# MultiSpikeHoldSchem.net
KiCad netlist of a schematic drawn in Altium Designer
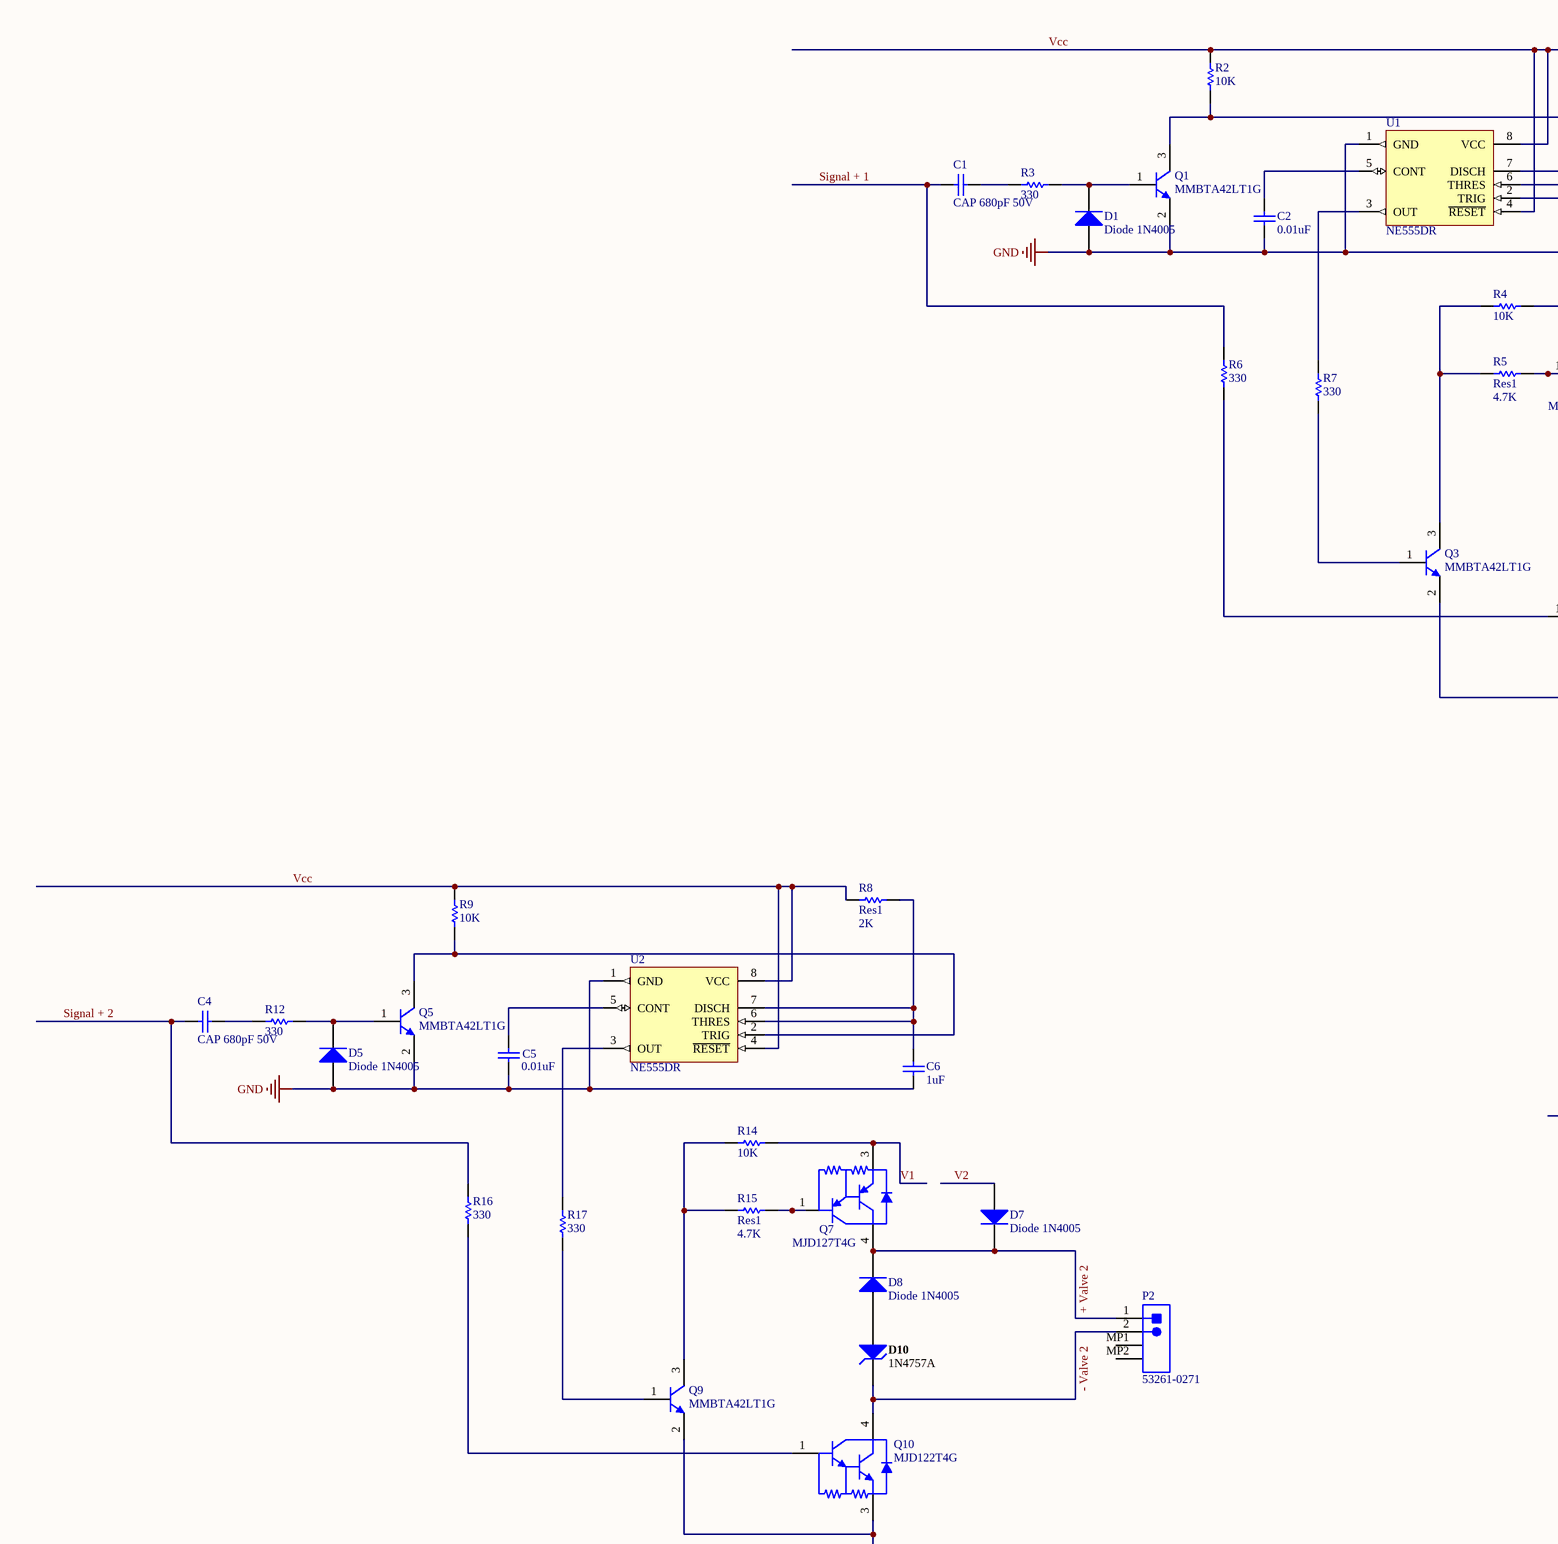
[diagram p0: MultiSpikeHoldSchem.SchDoc, top left]
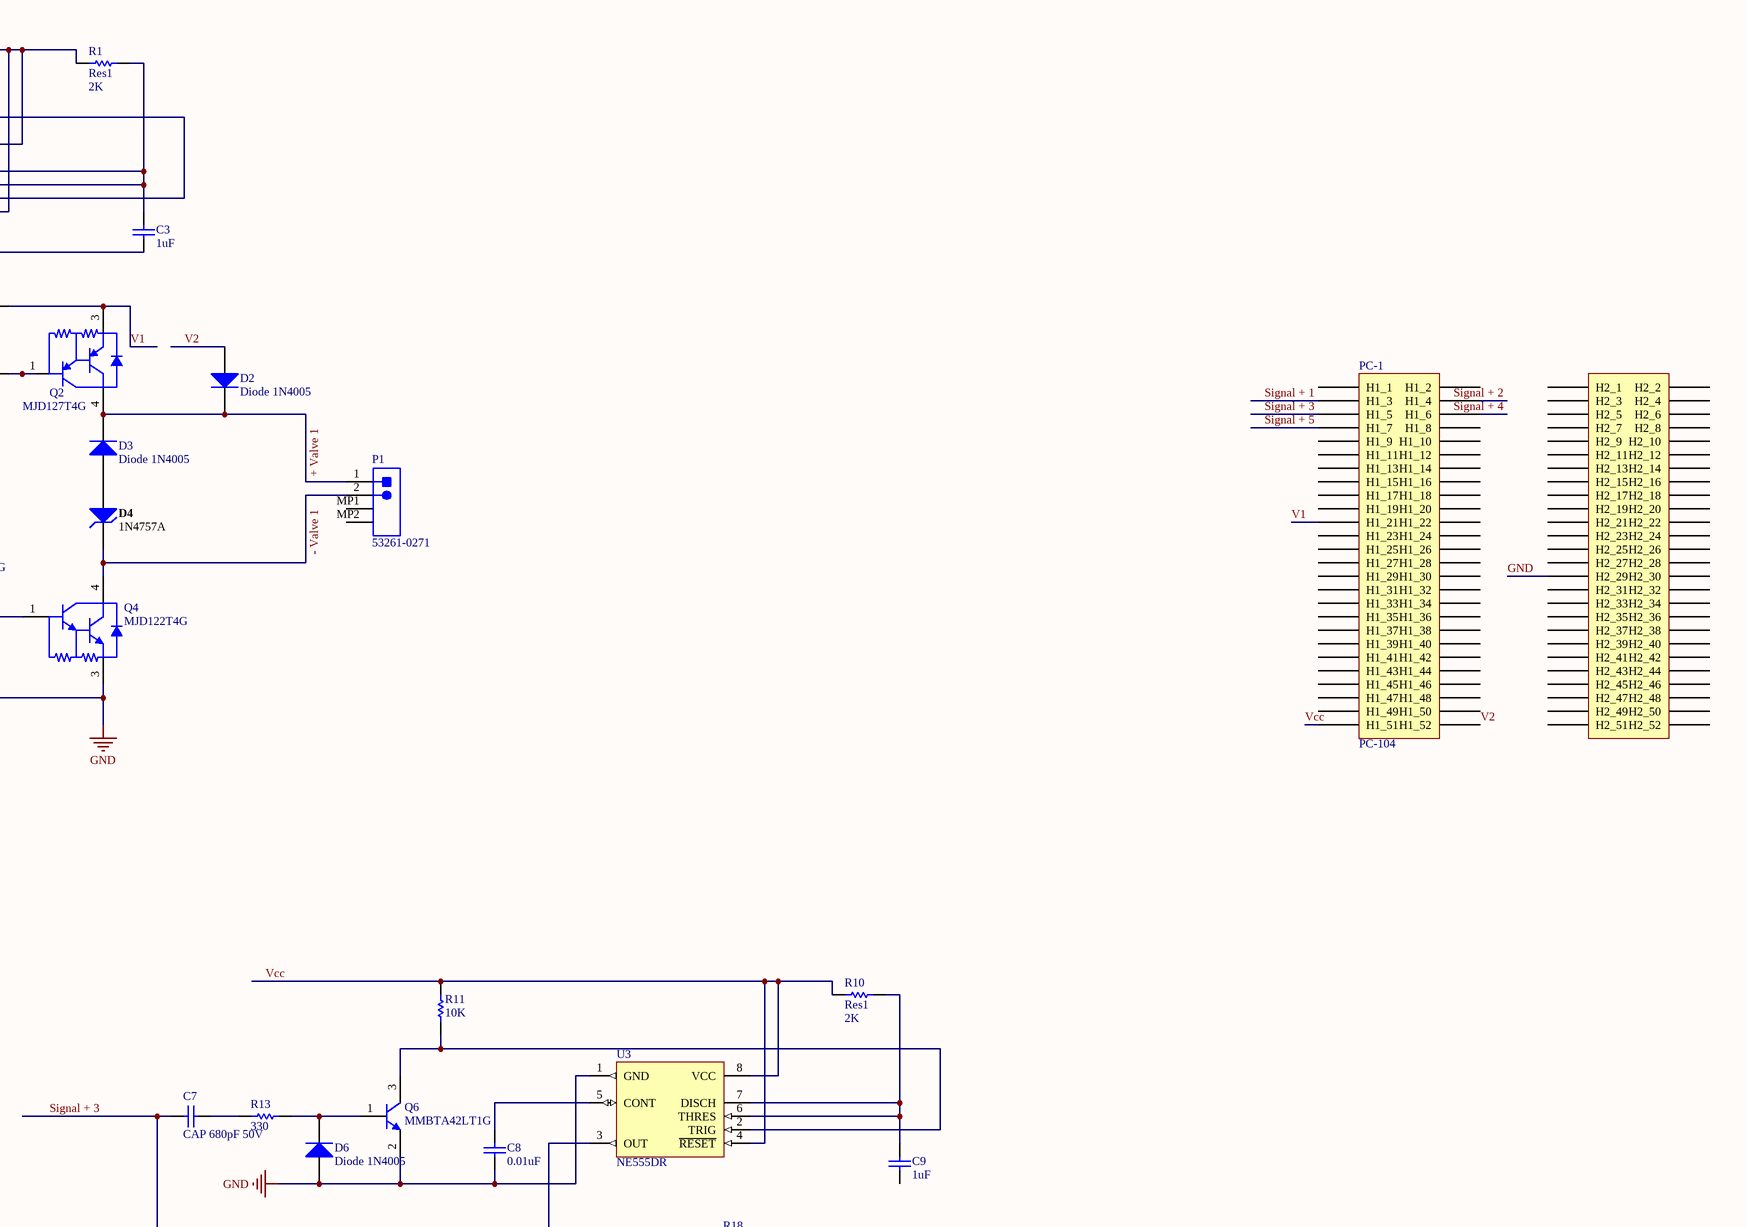
[diagram p1: MultiSpikeHoldSchem.SchDoc, top right]
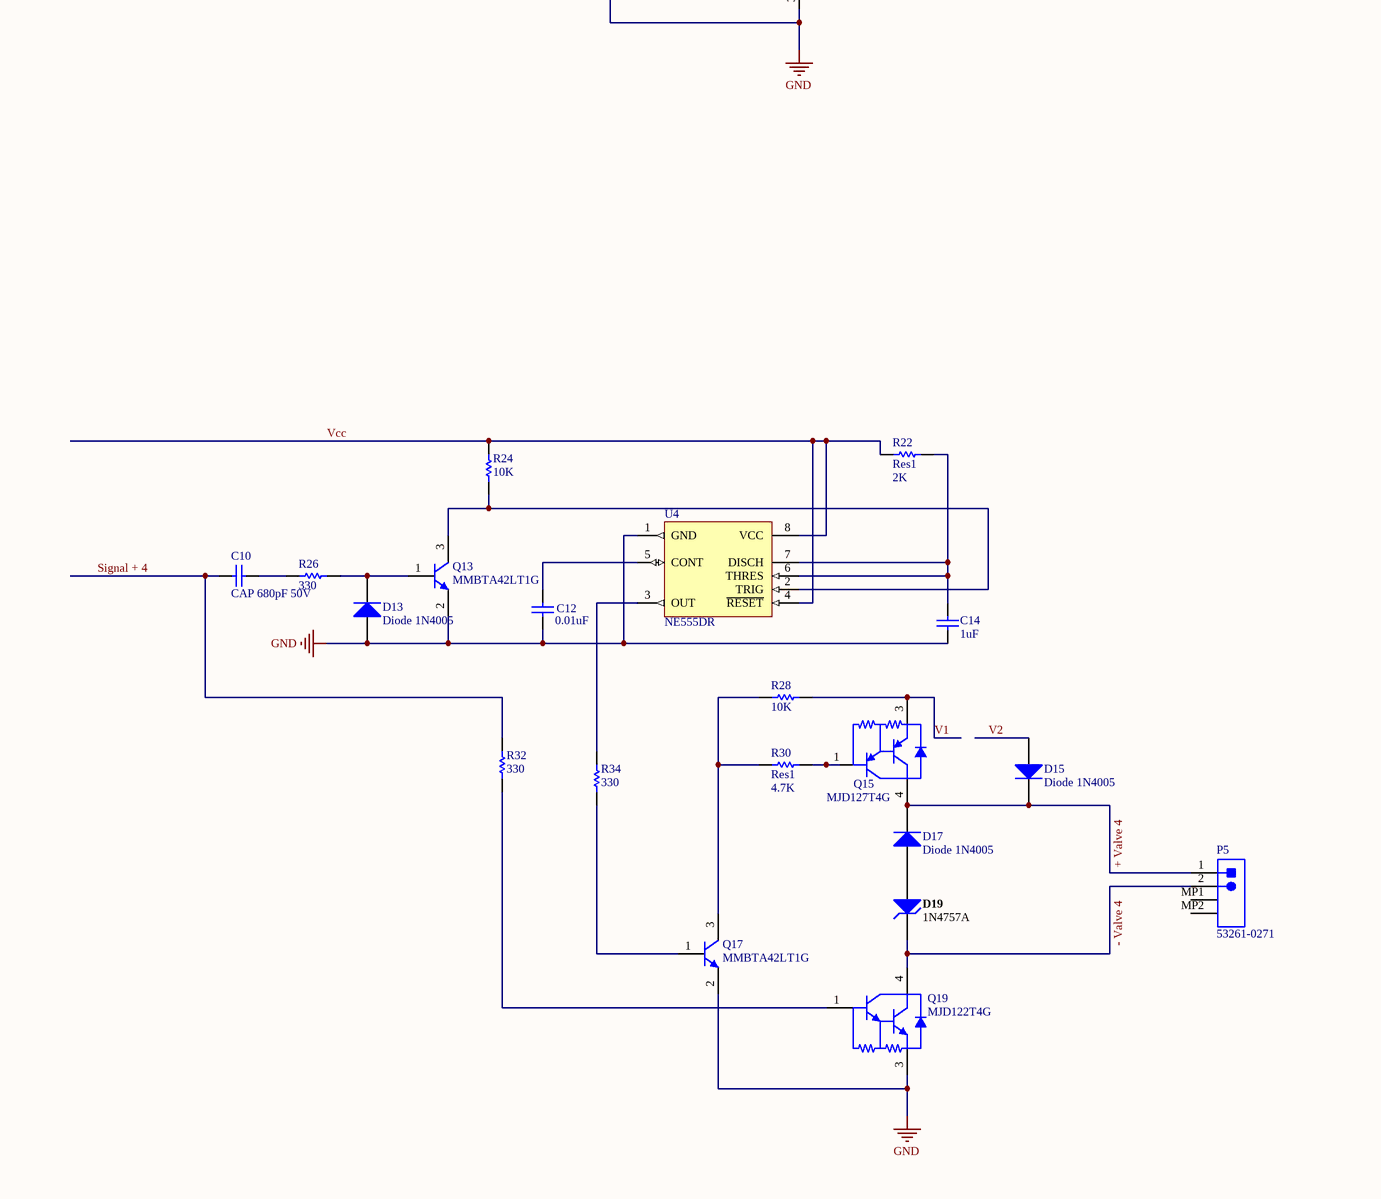
[diagram p2: MultiSpikeHoldSchem.SchDoc, bottom left]
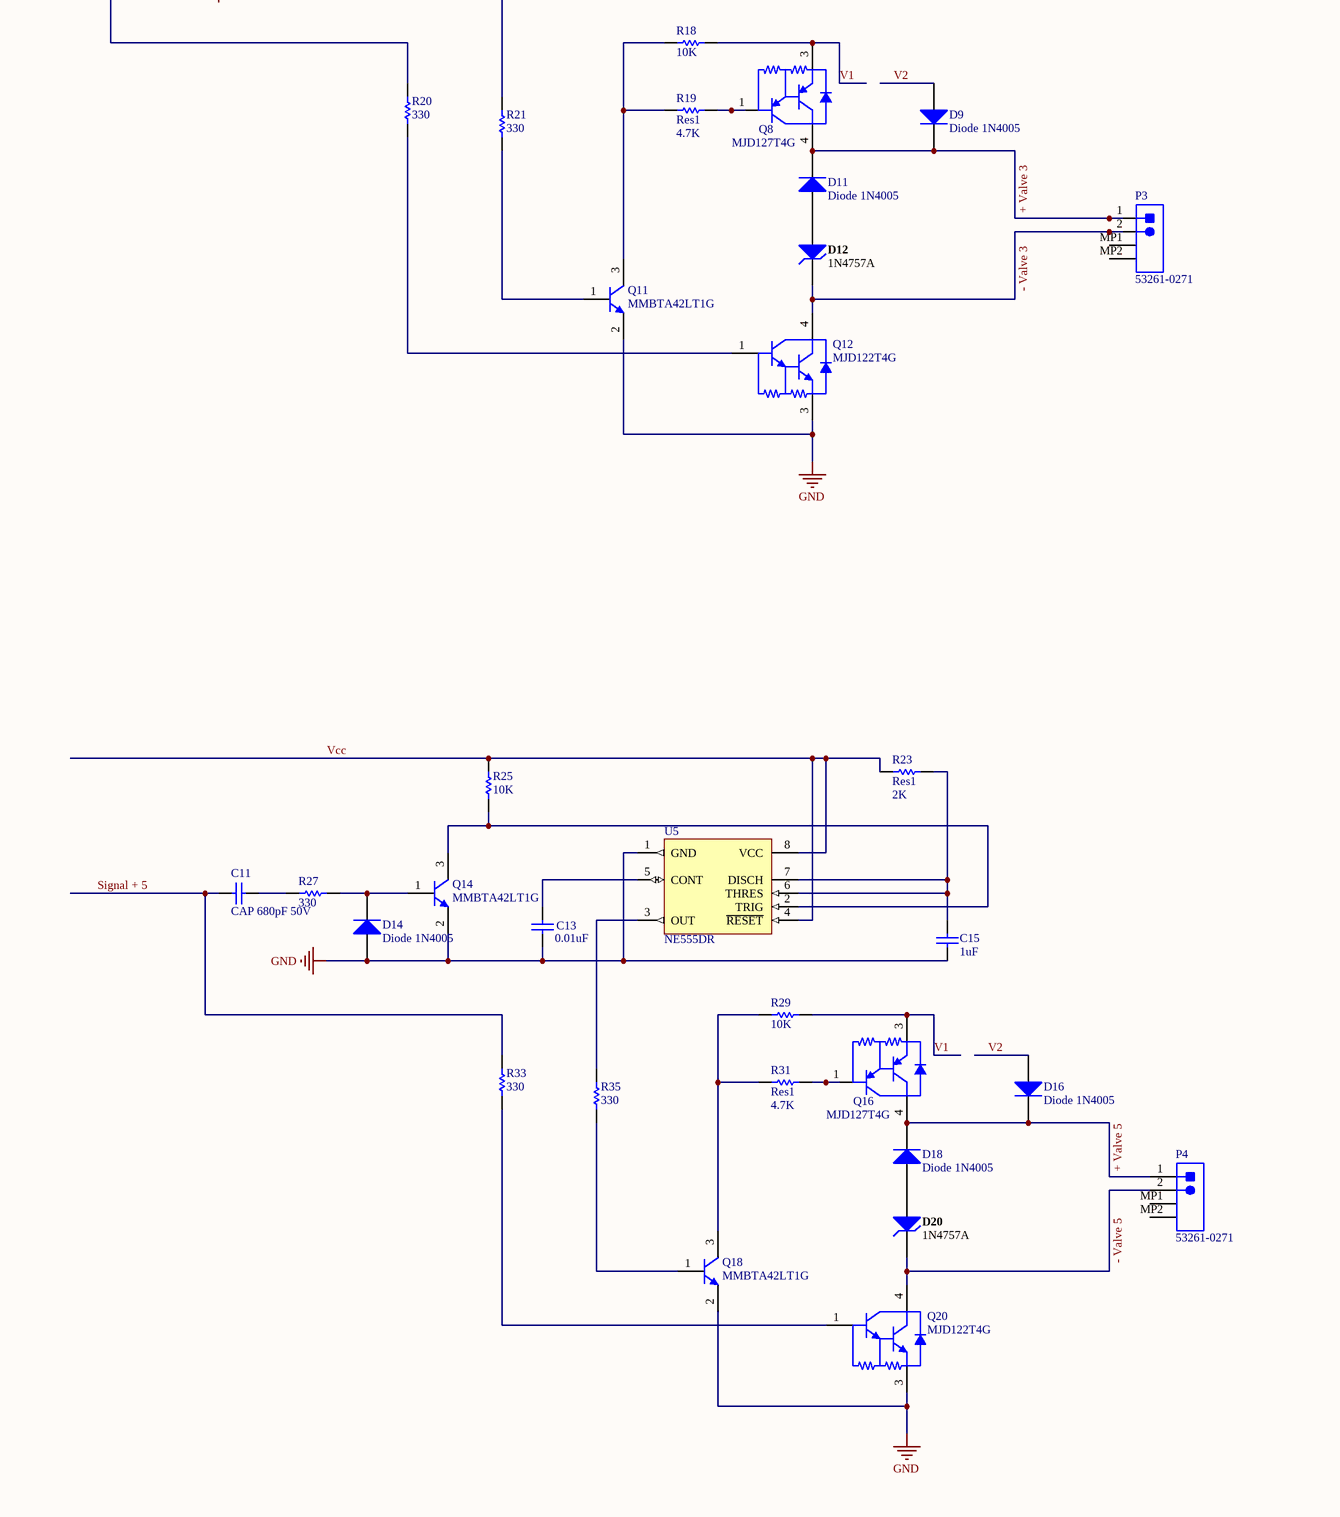
[diagram p3: MultiSpikeHoldSchem.SchDoc, bottom right]

(export (version "E")
  (design (tool "Eeschema 10.0.6"))
  (components
    (comp (ref "C1")
      (value "CAP 680pF 50V")
      (footprint "CAPC1812(4532)230_L")
      (description "CAP 680pF 50V ±5% 1812 (4532 Metric) Thickness 2.3mm SMD")
      (fields (field (name "TOLERANCE") "Â±5%"))
      (libsource (lib "Altium Content Vault") (part "CAP"))
    )
    (comp (ref "C2")
      (value "0.01uF")
      (footprint "CAPC2013X70X45ML10T25")
      (description "Chip Capacitor, 10 nF, +/- 10%, 50 V, -55 to 125 degC, 0805 (2012 Metric), RoHS, Tape and Reel")
      (fields (field (name "TOLERANCE") "10%") (field (name "MANUFACTURER") "Murata"))
      (libsource (lib "Altium Content Vault") (part "CAP-NP-2"))
    )
    (comp (ref "C3")
      (value "1uF")
      (footprint "CAPC1206(3216)110_L")
      (description "CAP 1uF 50V ±10% 1206 (3216 Metric) Thickness 1.1mm SMD")
      (fields (field (name "TOLERANCE") "Â±10%"))
      (libsource (lib "Altium Content Vault") (part "CAP"))
    )
    (comp (ref "C4")
      (value "CAP 680pF 50V")
      (footprint "CAPC1812(4532)230_L")
      (description "CAP 680pF 50V ±5% 1812 (4532 Metric) Thickness 2.3mm SMD")
      (fields (field (name "TOLERANCE") "Â±5%"))
      (libsource (lib "Altium Content Vault") (part "CAP"))
    )
    (comp (ref "C5")
      (value "0.01uF")
      (footprint "CAPC2013X70X45ML10T25")
      (description "Chip Capacitor, 10 nF, +/- 10%, 50 V, -55 to 125 degC, 0805 (2012 Metric), RoHS, Tape and Reel")
      (fields (field (name "TOLERANCE") "10%") (field (name "MANUFACTURER") "Murata"))
      (libsource (lib "Altium Content Vault") (part "CAP-NP-2"))
    )
    (comp (ref "C6")
      (value "1uF")
      (footprint "CAPC1206(3216)110_L")
      (description "CAP 1uF 50V ±10% 1206 (3216 Metric) Thickness 1.1mm SMD")
      (fields (field (name "TOLERANCE") "Â±10%"))
      (libsource (lib "Altium Content Vault") (part "CAP"))
    )
    (comp (ref "C7")
      (value "CAP 680pF 50V")
      (footprint "CAPC1812(4532)230_L")
      (description "CAP 680pF 50V ±5% 1812 (4532 Metric) Thickness 2.3mm SMD")
      (fields (field (name "TOLERANCE") "Â±5%"))
      (libsource (lib "Altium Content Vault") (part "CAP"))
    )
    (comp (ref "C8")
      (value "0.01uF")
      (footprint "CAPC2013X70X45ML10T25")
      (description "Chip Capacitor, 10 nF, +/- 10%, 50 V, -55 to 125 degC, 0805 (2012 Metric), RoHS, Tape and Reel")
      (fields (field (name "TOLERANCE") "10%") (field (name "MANUFACTURER") "Murata"))
      (libsource (lib "Altium Content Vault") (part "CAP-NP-2"))
    )
    (comp (ref "C9")
      (value "1uF")
      (footprint "CAPC1206(3216)110_L")
      (description "CAP 1uF 50V ±10% 1206 (3216 Metric) Thickness 1.1mm SMD")
      (fields (field (name "TOLERANCE") "Â±10%"))
      (libsource (lib "Altium Content Vault") (part "CAP"))
    )
    (comp (ref "C10")
      (value "CAP 680pF 50V")
      (footprint "CAPC1812(4532)230_L")
      (description "CAP 680pF 50V ±5% 1812 (4532 Metric) Thickness 2.3mm SMD")
      (fields (field (name "TOLERANCE") "Â±5%"))
      (libsource (lib "Altium Content Vault") (part "CAP"))
    )
    (comp (ref "C11")
      (value "CAP 680pF 50V")
      (footprint "CAPC1812(4532)230_L")
      (description "CAP 680pF 50V ±5% 1812 (4532 Metric) Thickness 2.3mm SMD")
      (fields (field (name "TOLERANCE") "Â±5%"))
      (libsource (lib "Altium Content Vault") (part "CAP"))
    )
    (comp (ref "C12")
      (value "0.01uF")
      (footprint "CAPC2013X70X45ML10T25")
      (description "Chip Capacitor, 10 nF, +/- 10%, 50 V, -55 to 125 degC, 0805 (2012 Metric), RoHS, Tape and Reel")
      (fields (field (name "TOLERANCE") "10%") (field (name "MANUFACTURER") "Murata"))
      (libsource (lib "Altium Content Vault") (part "CAP-NP-2"))
    )
    (comp (ref "C13")
      (value "0.01uF")
      (footprint "CAPC2013X70X45ML10T25")
      (description "Chip Capacitor, 10 nF, +/- 10%, 50 V, -55 to 125 degC, 0805 (2012 Metric), RoHS, Tape and Reel")
      (fields (field (name "TOLERANCE") "10%") (field (name "MANUFACTURER") "Murata"))
      (libsource (lib "Altium Content Vault") (part "CAP-NP-2"))
    )
    (comp (ref "C14")
      (value "1uF")
      (footprint "CAPC1206(3216)110_L")
      (description "CAP 1uF 50V ±10% 1206 (3216 Metric) Thickness 1.1mm SMD")
      (fields (field (name "TOLERANCE") "Â±10%"))
      (libsource (lib "Altium Content Vault") (part "CAP"))
    )
    (comp (ref "C15")
      (value "1uF")
      (footprint "CAPC1206(3216)110_L")
      (description "CAP 1uF 50V ±10% 1206 (3216 Metric) Thickness 1.1mm SMD")
      (fields (field (name "TOLERANCE") "Â±10%"))
      (libsource (lib "Altium Content Vault") (part "CAP"))
    )
    (comp (ref "D1")
      (value "Diode 1N4005")
      (footprint "DO-41")
      (description "1 Amp General Purpose Rectifier")
      (fields (field (name "PUBLISHER") "Altium Limited"))
      (libsource (lib "Miscellaneous Devices") (part "Diode 1N4005"))
    )
    (comp (ref "D2")
      (value "Diode 1N4005")
      (footprint "DO-41")
      (description "1 Amp General Purpose Rectifier")
      (fields (field (name "PUBLISHER") "Altium Limited"))
      (libsource (lib "Miscellaneous Devices") (part "Diode 1N4005"))
    )
    (comp (ref "D3")
      (value "Diode 1N4005")
      (footprint "DO-41")
      (description "1 Amp General Purpose Rectifier")
      (fields (field (name "PUBLISHER") "Altium Limited"))
      (libsource (lib "Miscellaneous Devices") (part "Diode 1N4005"))
    )
    (comp (ref "D4")
      (value "1N4757A")
      (footprint "FAIR-DO-41-2_V")
      (description "Zener Diode, 51V, 1W, 5%, -65 to 200 degC, 2-Pin DO-41, Body 2.72 x 5.2 mm, RoHS")
      (fields (field (name "MANUFACTURER") "Fairchild Semiconductor") (field (name "TOLERANCE") "5%"))
      (libsource (lib "Altium Content Vault") (part "FAIR-DZEN-A1K2-2"))
    )
    (comp (ref "D5")
      (value "Diode 1N4005")
      (footprint "DO-41")
      (description "1 Amp General Purpose Rectifier")
      (fields (field (name "PUBLISHER") "Altium Limited"))
      (libsource (lib "Miscellaneous Devices") (part "Diode 1N4005"))
    )
    (comp (ref "D6")
      (value "Diode 1N4005")
      (footprint "DO-41")
      (description "1 Amp General Purpose Rectifier")
      (fields (field (name "PUBLISHER") "Altium Limited"))
      (libsource (lib "Miscellaneous Devices") (part "Diode 1N4005"))
    )
    (comp (ref "D7")
      (value "Diode 1N4005")
      (footprint "DO-41")
      (description "1 Amp General Purpose Rectifier")
      (fields (field (name "PUBLISHER") "Altium Limited"))
      (libsource (lib "Miscellaneous Devices") (part "Diode 1N4005"))
    )
    (comp (ref "D8")
      (value "Diode 1N4005")
      (footprint "DO-41")
      (description "1 Amp General Purpose Rectifier")
      (fields (field (name "PUBLISHER") "Altium Limited"))
      (libsource (lib "Miscellaneous Devices") (part "Diode 1N4005"))
    )
    (comp (ref "D9")
      (value "Diode 1N4005")
      (footprint "DO-41")
      (description "1 Amp General Purpose Rectifier")
      (fields (field (name "PUBLISHER") "Altium Limited"))
      (libsource (lib "Miscellaneous Devices") (part "Diode 1N4005"))
    )
    (comp (ref "D10")
      (value "1N4757A")
      (footprint "FAIR-DO-41-2_V")
      (description "Zener Diode, 51V, 1W, 5%, -65 to 200 degC, 2-Pin DO-41, Body 2.72 x 5.2 mm, RoHS")
      (fields (field (name "MANUFACTURER") "Fairchild Semiconductor") (field (name "TOLERANCE") "5%"))
      (libsource (lib "Altium Content Vault") (part "FAIR-DZEN-A1K2-2"))
    )
    (comp (ref "D11")
      (value "Diode 1N4005")
      (footprint "DO-41")
      (description "1 Amp General Purpose Rectifier")
      (fields (field (name "PUBLISHER") "Altium Limited"))
      (libsource (lib "Miscellaneous Devices") (part "Diode 1N4005"))
    )
    (comp (ref "D12")
      (value "1N4757A")
      (footprint "FAIR-DO-41-2_V")
      (description "Zener Diode, 51V, 1W, 5%, -65 to 200 degC, 2-Pin DO-41, Body 2.72 x 5.2 mm, RoHS")
      (fields (field (name "MANUFACTURER") "Fairchild Semiconductor") (field (name "TOLERANCE") "5%"))
      (libsource (lib "Altium Content Vault") (part "FAIR-DZEN-A1K2-2"))
    )
    (comp (ref "D13")
      (value "Diode 1N4005")
      (footprint "DO-41")
      (description "1 Amp General Purpose Rectifier")
      (fields (field (name "PUBLISHER") "Altium Limited"))
      (libsource (lib "Miscellaneous Devices") (part "Diode 1N4005"))
    )
    (comp (ref "D14")
      (value "Diode 1N4005")
      (footprint "DO-41")
      (description "1 Amp General Purpose Rectifier")
      (fields (field (name "PUBLISHER") "Altium Limited"))
      (libsource (lib "Miscellaneous Devices") (part "Diode 1N4005"))
    )
    (comp (ref "D15")
      (value "Diode 1N4005")
      (footprint "DO-41")
      (description "1 Amp General Purpose Rectifier")
      (fields (field (name "PUBLISHER") "Altium Limited"))
      (libsource (lib "Miscellaneous Devices") (part "Diode 1N4005"))
    )
    (comp (ref "D16")
      (value "Diode 1N4005")
      (footprint "DO-41")
      (description "1 Amp General Purpose Rectifier")
      (fields (field (name "PUBLISHER") "Altium Limited"))
      (libsource (lib "Miscellaneous Devices") (part "Diode 1N4005"))
    )
    (comp (ref "D17")
      (value "Diode 1N4005")
      (footprint "DO-41")
      (description "1 Amp General Purpose Rectifier")
      (fields (field (name "PUBLISHER") "Altium Limited"))
      (libsource (lib "Miscellaneous Devices") (part "Diode 1N4005"))
    )
    (comp (ref "D18")
      (value "Diode 1N4005")
      (footprint "DO-41")
      (description "1 Amp General Purpose Rectifier")
      (fields (field (name "PUBLISHER") "Altium Limited"))
      (libsource (lib "Miscellaneous Devices") (part "Diode 1N4005"))
    )
    (comp (ref "D19")
      (value "1N4757A")
      (footprint "FAIR-DO-41-2_V")
      (description "Zener Diode, 51V, 1W, 5%, -65 to 200 degC, 2-Pin DO-41, Body 2.72 x 5.2 mm, RoHS")
      (fields (field (name "MANUFACTURER") "Fairchild Semiconductor") (field (name "TOLERANCE") "5%"))
      (libsource (lib "Altium Content Vault") (part "FAIR-DZEN-A1K2-2"))
    )
    (comp (ref "D20")
      (value "1N4757A")
      (footprint "FAIR-DO-41-2_V")
      (description "Zener Diode, 51V, 1W, 5%, -65 to 200 degC, 2-Pin DO-41, Body 2.72 x 5.2 mm, RoHS")
      (fields (field (name "MANUFACTURER") "Fairchild Semiconductor") (field (name "TOLERANCE") "5%"))
      (libsource (lib "Altium Content Vault") (part "FAIR-DZEN-A1K2-2"))
    )
    (comp (ref "P1")
      (value "53261-0271")
      (footprint "MOLX-53261-0271_V")
      (description "PicoBlade(TM) Header, Right Angle, -40 to 85 degC, 2-Pin SMD, RoHS, Tape and Reel")
      (fields (field (name "MANUFACTURER") "Molex"))
      (libsource (lib "Altium Content Vault") (part "CN-1P-2M-R2"))
    )
    (comp (ref "P2")
      (value "53261-0271")
      (footprint "MOLX-53261-0271_V")
      (description "PicoBlade(TM) Header, Right Angle, -40 to 85 degC, 2-Pin SMD, RoHS, Tape and Reel")
      (fields (field (name "MANUFACTURER") "Molex"))
      (libsource (lib "Altium Content Vault") (part "CN-1P-2M-R2"))
    )
    (comp (ref "P3")
      (value "53261-0271")
      (footprint "MOLX-53261-0271_V")
      (description "PicoBlade(TM) Header, Right Angle, -40 to 85 degC, 2-Pin SMD, RoHS, Tape and Reel")
      (fields (field (name "MANUFACTURER") "Molex"))
      (libsource (lib "Altium Content Vault") (part "CN-1P-2M-R2"))
    )
    (comp (ref "P4")
      (value "53261-0271")
      (footprint "MOLX-53261-0271_V")
      (description "PicoBlade(TM) Header, Right Angle, -40 to 85 degC, 2-Pin SMD, RoHS, Tape and Reel")
      (fields (field (name "MANUFACTURER") "Molex"))
      (libsource (lib "Altium Content Vault") (part "CN-1P-2M-R2"))
    )
    (comp (ref "P5")
      (value "53261-0271")
      (footprint "MOLX-53261-0271_V")
      (description "PicoBlade(TM) Header, Right Angle, -40 to 85 degC, 2-Pin SMD, RoHS, Tape and Reel")
      (fields (field (name "MANUFACTURER") "Molex"))
      (libsource (lib "Altium Content Vault") (part "CN-1P-2M-R2"))
    )
    (comp (ref "PC-1")
      (value "PC-104")
      (footprint "PC-104FOOTPRINT")
      (libsource (lib "UmbilicalBoardV3") (part "PC-104"))
    )
    (comp (ref "Q1")
      (value "MMBTA42LT1G")
      (footprint "ONSC-SOT-23-3-318-08_V")
      (description "High Voltage Transistor, NPN Silicon, 3-Pin SOT-23, Pb-Free, Tape and Reel")
      (fields (field (name "MANUFACTURER") "On Semiconductor"))
      (libsource (lib "Altium Content Vault") (part "CMP-1048-00662-1"))
    )
    (comp (ref "Q2")
      (value "MJD127T4G")
      (footprint "ONSC-DPAK-3-369C-01_V")
      (description "Complementary Darlington Power Transistor, 3-Pin DPAK, Pb-Free, Tape and Reel")
      (fields (field (name "MANUFACTURER") "On Semiconductor"))
      (libsource (lib "Altium Content Vault") (part "CMP-1047-00009-1"))
    )
    (comp (ref "Q3")
      (value "MMBTA42LT1G")
      (footprint "ONSC-SOT-23-3-318-08_V")
      (description "High Voltage Transistor, NPN Silicon, 3-Pin SOT-23, Pb-Free, Tape and Reel")
      (fields (field (name "MANUFACTURER") "On Semiconductor"))
      (libsource (lib "Altium Content Vault") (part "CMP-1048-00662-1"))
    )
    (comp (ref "Q4")
      (value "MJD122T4G")
      (footprint "ONSC-DPAK-3-369C-01_V")
      (description "Complementary Darlington Power Transistor, 3-Pin DPAK, Pb-Free, Tape and Reel")
      (fields (field (name "MANUFACTURER") "On Semiconductor"))
      (libsource (lib "Altium Content Vault") (part "CMP-1047-00007-1"))
    )
    (comp (ref "Q5")
      (value "MMBTA42LT1G")
      (footprint "ONSC-SOT-23-3-318-08_V")
      (description "High Voltage Transistor, NPN Silicon, 3-Pin SOT-23, Pb-Free, Tape and Reel")
      (fields (field (name "MANUFACTURER") "On Semiconductor"))
      (libsource (lib "Altium Content Vault") (part "CMP-1048-00662-1"))
    )
    (comp (ref "Q6")
      (value "MMBTA42LT1G")
      (footprint "ONSC-SOT-23-3-318-08_V")
      (description "High Voltage Transistor, NPN Silicon, 3-Pin SOT-23, Pb-Free, Tape and Reel")
      (fields (field (name "MANUFACTURER") "On Semiconductor"))
      (libsource (lib "Altium Content Vault") (part "CMP-1048-00662-1"))
    )
    (comp (ref "Q7")
      (value "MJD127T4G")
      (footprint "ONSC-DPAK-3-369C-01_V")
      (description "Complementary Darlington Power Transistor, 3-Pin DPAK, Pb-Free, Tape and Reel")
      (fields (field (name "MANUFACTURER") "On Semiconductor"))
      (libsource (lib "Altium Content Vault") (part "CMP-1047-00009-1"))
    )
    (comp (ref "Q8")
      (value "MJD127T4G")
      (footprint "ONSC-DPAK-3-369C-01_V")
      (description "Complementary Darlington Power Transistor, 3-Pin DPAK, Pb-Free, Tape and Reel")
      (fields (field (name "MANUFACTURER") "On Semiconductor"))
      (libsource (lib "Altium Content Vault") (part "CMP-1047-00009-1"))
    )
    (comp (ref "Q9")
      (value "MMBTA42LT1G")
      (footprint "ONSC-SOT-23-3-318-08_V")
      (description "High Voltage Transistor, NPN Silicon, 3-Pin SOT-23, Pb-Free, Tape and Reel")
      (fields (field (name "MANUFACTURER") "On Semiconductor"))
      (libsource (lib "Altium Content Vault") (part "CMP-1048-00662-1"))
    )
    (comp (ref "Q10")
      (value "MJD122T4G")
      (footprint "ONSC-DPAK-3-369C-01_V")
      (description "Complementary Darlington Power Transistor, 3-Pin DPAK, Pb-Free, Tape and Reel")
      (fields (field (name "MANUFACTURER") "On Semiconductor"))
      (libsource (lib "Altium Content Vault") (part "CMP-1047-00007-1"))
    )
    (comp (ref "Q11")
      (value "MMBTA42LT1G")
      (footprint "ONSC-SOT-23-3-318-08_V")
      (description "High Voltage Transistor, NPN Silicon, 3-Pin SOT-23, Pb-Free, Tape and Reel")
      (fields (field (name "MANUFACTURER") "On Semiconductor"))
      (libsource (lib "Altium Content Vault") (part "CMP-1048-00662-1"))
    )
    (comp (ref "Q12")
      (value "MJD122T4G")
      (footprint "ONSC-DPAK-3-369C-01_V")
      (description "Complementary Darlington Power Transistor, 3-Pin DPAK, Pb-Free, Tape and Reel")
      (fields (field (name "MANUFACTURER") "On Semiconductor"))
      (libsource (lib "Altium Content Vault") (part "CMP-1047-00007-1"))
    )
    (comp (ref "Q13")
      (value "MMBTA42LT1G")
      (footprint "ONSC-SOT-23-3-318-08_V")
      (description "High Voltage Transistor, NPN Silicon, 3-Pin SOT-23, Pb-Free, Tape and Reel")
      (fields (field (name "MANUFACTURER") "On Semiconductor"))
      (libsource (lib "Altium Content Vault") (part "CMP-1048-00662-1"))
    )
    (comp (ref "Q14")
      (value "MMBTA42LT1G")
      (footprint "ONSC-SOT-23-3-318-08_V")
      (description "High Voltage Transistor, NPN Silicon, 3-Pin SOT-23, Pb-Free, Tape and Reel")
      (fields (field (name "MANUFACTURER") "On Semiconductor"))
      (libsource (lib "Altium Content Vault") (part "CMP-1048-00662-1"))
    )
    (comp (ref "Q15")
      (value "MJD127T4G")
      (footprint "ONSC-DPAK-3-369C-01_V")
      (description "Complementary Darlington Power Transistor, 3-Pin DPAK, Pb-Free, Tape and Reel")
      (fields (field (name "MANUFACTURER") "On Semiconductor"))
      (libsource (lib "Altium Content Vault") (part "CMP-1047-00009-1"))
    )
    (comp (ref "Q16")
      (value "MJD127T4G")
      (footprint "ONSC-DPAK-3-369C-01_V")
      (description "Complementary Darlington Power Transistor, 3-Pin DPAK, Pb-Free, Tape and Reel")
      (fields (field (name "MANUFACTURER") "On Semiconductor"))
      (libsource (lib "Altium Content Vault") (part "CMP-1047-00009-1"))
    )
    (comp (ref "Q17")
      (value "MMBTA42LT1G")
      (footprint "ONSC-SOT-23-3-318-08_V")
      (description "High Voltage Transistor, NPN Silicon, 3-Pin SOT-23, Pb-Free, Tape and Reel")
      (fields (field (name "MANUFACTURER") "On Semiconductor"))
      (libsource (lib "Altium Content Vault") (part "CMP-1048-00662-1"))
    )
    (comp (ref "Q18")
      (value "MMBTA42LT1G")
      (footprint "ONSC-SOT-23-3-318-08_V")
      (description "High Voltage Transistor, NPN Silicon, 3-Pin SOT-23, Pb-Free, Tape and Reel")
      (fields (field (name "MANUFACTURER") "On Semiconductor"))
      (libsource (lib "Altium Content Vault") (part "CMP-1048-00662-1"))
    )
    (comp (ref "Q19")
      (value "MJD122T4G")
      (footprint "ONSC-DPAK-3-369C-01_V")
      (description "Complementary Darlington Power Transistor, 3-Pin DPAK, Pb-Free, Tape and Reel")
      (fields (field (name "MANUFACTURER") "On Semiconductor"))
      (libsource (lib "Altium Content Vault") (part "CMP-1047-00007-1"))
    )
    (comp (ref "Q20")
      (value "MJD122T4G")
      (footprint "ONSC-DPAK-3-369C-01_V")
      (description "Complementary Darlington Power Transistor, 3-Pin DPAK, Pb-Free, Tape and Reel")
      (fields (field (name "MANUFACTURER") "On Semiconductor"))
      (libsource (lib "Altium Content Vault") (part "CMP-1047-00007-1"))
    )
    (comp (ref "R1")
      (value "Res1")
      (footprint "AXIAL-0.3")
      (description "Resistor")
      (fields (field (name "ALTIUM_VALUE") "2K") (field (name "PUBLISHER") "Altium Limited"))
      (libsource (lib "Miscellaneous Devices") (part "Res1"))
    )
    (comp (ref "R2")
      (value "10K")
      (footprint "RESC1608X55X25ML10T15")
      (description "Chip Resistor, 10 KOhm, +/- 1%, 01 W, -55 to 155 degC, 0603 (1608 Metric), RoHS, Tape and Reel")
      (fields (field (name "MANUFACTURER") "Yageo") (field (name "TOLERANCE") "1%"))
      (libsource (lib "Altium Content Vault") (part "RES-2"))
    )
    (comp (ref "R3")
      (value "330")
      (footprint "RESC3116X65X40LL10T20")
      (description "Chip Resistor, 330 Ohm, +/- 1%, 250 mW, -55 to 155 degC, 1206 (3216 Metric), RoHS, Tape and Reel")
      (fields (field (name "MANUFACTURER") "Yageo") (field (name "TOLERANCE") "1%"))
      (libsource (lib "Altium Content Vault") (part "RES-2"))
    )
    (comp (ref "R4")
      (value "10K")
      (footprint "RESC1608X55X25ML10T15")
      (description "Chip Resistor, 10 KOhm, +/- 1%, 01 W, -55 to 155 degC, 0603 (1608 Metric), RoHS, Tape and Reel")
      (fields (field (name "MANUFACTURER") "Yageo") (field (name "TOLERANCE") "1%"))
      (libsource (lib "Altium Content Vault") (part "RES-2"))
    )
    (comp (ref "R5")
      (value "Res1")
      (footprint "AXIAL-0.3")
      (description "Resistor")
      (fields (field (name "ALTIUM_VALUE") "4.7K") (field (name "PUBLISHER") "Altium Limited"))
      (libsource (lib "Miscellaneous Devices") (part "Res1"))
    )
    (comp (ref "R6")
      (value "330")
      (footprint "RESC3116X65X40LL10T20")
      (description "Chip Resistor, 330 Ohm, +/- 1%, 250 mW, -55 to 155 degC, 1206 (3216 Metric), RoHS, Tape and Reel")
      (fields (field (name "MANUFACTURER") "Yageo") (field (name "TOLERANCE") "1%"))
      (libsource (lib "Altium Content Vault") (part "RES-2"))
    )
    (comp (ref "R7")
      (value "330")
      (footprint "RESC3116X65X40LL10T20")
      (description "Chip Resistor, 330 Ohm, +/- 1%, 250 mW, -55 to 155 degC, 1206 (3216 Metric), RoHS, Tape and Reel")
      (fields (field (name "MANUFACTURER") "Yageo") (field (name "TOLERANCE") "1%"))
      (libsource (lib "Altium Content Vault") (part "RES-2"))
    )
    (comp (ref "R8")
      (value "Res1")
      (footprint "AXIAL-0.3")
      (description "Resistor")
      (fields (field (name "ALTIUM_VALUE") "2K") (field (name "PUBLISHER") "Altium Limited"))
      (libsource (lib "Miscellaneous Devices") (part "Res1"))
    )
    (comp (ref "R9")
      (value "10K")
      (footprint "RESC1608X55X25ML10T15")
      (description "Chip Resistor, 10 KOhm, +/- 1%, 01 W, -55 to 155 degC, 0603 (1608 Metric), RoHS, Tape and Reel")
      (fields (field (name "MANUFACTURER") "Yageo") (field (name "TOLERANCE") "1%"))
      (libsource (lib "Altium Content Vault") (part "RES-2"))
    )
    (comp (ref "R10")
      (value "Res1")
      (footprint "AXIAL-0.3")
      (description "Resistor")
      (fields (field (name "ALTIUM_VALUE") "2K") (field (name "PUBLISHER") "Altium Limited"))
      (libsource (lib "Miscellaneous Devices") (part "Res1"))
    )
    (comp (ref "R11")
      (value "10K")
      (footprint "RESC1608X55X25ML10T15")
      (description "Chip Resistor, 10 KOhm, +/- 1%, 01 W, -55 to 155 degC, 0603 (1608 Metric), RoHS, Tape and Reel")
      (fields (field (name "MANUFACTURER") "Yageo") (field (name "TOLERANCE") "1%"))
      (libsource (lib "Altium Content Vault") (part "RES-2"))
    )
    (comp (ref "R12")
      (value "330")
      (footprint "RESC3116X65X40LL10T20")
      (description "Chip Resistor, 330 Ohm, +/- 1%, 250 mW, -55 to 155 degC, 1206 (3216 Metric), RoHS, Tape and Reel")
      (fields (field (name "MANUFACTURER") "Yageo") (field (name "TOLERANCE") "1%"))
      (libsource (lib "Altium Content Vault") (part "RES-2"))
    )
    (comp (ref "R13")
      (value "330")
      (footprint "RESC3116X65X40LL10T20")
      (description "Chip Resistor, 330 Ohm, +/- 1%, 250 mW, -55 to 155 degC, 1206 (3216 Metric), RoHS, Tape and Reel")
      (fields (field (name "MANUFACTURER") "Yageo") (field (name "TOLERANCE") "1%"))
      (libsource (lib "Altium Content Vault") (part "RES-2"))
    )
    (comp (ref "R14")
      (value "10K")
      (footprint "RESC1608X55X25ML10T15")
      (description "Chip Resistor, 10 KOhm, +/- 1%, 01 W, -55 to 155 degC, 0603 (1608 Metric), RoHS, Tape and Reel")
      (fields (field (name "MANUFACTURER") "Yageo") (field (name "TOLERANCE") "1%"))
      (libsource (lib "Altium Content Vault") (part "RES-2"))
    )
    (comp (ref "R15")
      (value "Res1")
      (footprint "AXIAL-0.3")
      (description "Resistor")
      (fields (field (name "ALTIUM_VALUE") "4.7K") (field (name "PUBLISHER") "Altium Limited"))
      (libsource (lib "Miscellaneous Devices") (part "Res1"))
    )
    (comp (ref "R16")
      (value "330")
      (footprint "RESC3116X65X40LL10T20")
      (description "Chip Resistor, 330 Ohm, +/- 1%, 250 mW, -55 to 155 degC, 1206 (3216 Metric), RoHS, Tape and Reel")
      (fields (field (name "MANUFACTURER") "Yageo") (field (name "TOLERANCE") "1%"))
      (libsource (lib "Altium Content Vault") (part "RES-2"))
    )
    (comp (ref "R17")
      (value "330")
      (footprint "RESC3116X65X40LL10T20")
      (description "Chip Resistor, 330 Ohm, +/- 1%, 250 mW, -55 to 155 degC, 1206 (3216 Metric), RoHS, Tape and Reel")
      (fields (field (name "MANUFACTURER") "Yageo") (field (name "TOLERANCE") "1%"))
      (libsource (lib "Altium Content Vault") (part "RES-2"))
    )
    (comp (ref "R18")
      (value "10K")
      (footprint "RESC1608X55X25ML10T15")
      (description "Chip Resistor, 10 KOhm, +/- 1%, 01 W, -55 to 155 degC, 0603 (1608 Metric), RoHS, Tape and Reel")
      (fields (field (name "MANUFACTURER") "Yageo") (field (name "TOLERANCE") "1%"))
      (libsource (lib "Altium Content Vault") (part "RES-2"))
    )
    (comp (ref "R19")
      (value "Res1")
      (footprint "AXIAL-0.3")
      (description "Resistor")
      (fields (field (name "ALTIUM_VALUE") "4.7K") (field (name "PUBLISHER") "Altium Limited"))
      (libsource (lib "Miscellaneous Devices") (part "Res1"))
    )
    (comp (ref "R20")
      (value "330")
      (footprint "RESC3116X65X40LL10T20")
      (description "Chip Resistor, 330 Ohm, +/- 1%, 250 mW, -55 to 155 degC, 1206 (3216 Metric), RoHS, Tape and Reel")
      (fields (field (name "MANUFACTURER") "Yageo") (field (name "TOLERANCE") "1%"))
      (libsource (lib "Altium Content Vault") (part "RES-2"))
    )
    (comp (ref "R21")
      (value "330")
      (footprint "RESC3116X65X40LL10T20")
      (description "Chip Resistor, 330 Ohm, +/- 1%, 250 mW, -55 to 155 degC, 1206 (3216 Metric), RoHS, Tape and Reel")
      (fields (field (name "MANUFACTURER") "Yageo") (field (name "TOLERANCE") "1%"))
      (libsource (lib "Altium Content Vault") (part "RES-2"))
    )
    (comp (ref "R22")
      (value "Res1")
      (footprint "AXIAL-0.3")
      (description "Resistor")
      (fields (field (name "ALTIUM_VALUE") "2K") (field (name "PUBLISHER") "Altium Limited"))
      (libsource (lib "Miscellaneous Devices") (part "Res1"))
    )
    (comp (ref "R23")
      (value "Res1")
      (footprint "AXIAL-0.3")
      (description "Resistor")
      (fields (field (name "ALTIUM_VALUE") "2K") (field (name "PUBLISHER") "Altium Limited"))
      (libsource (lib "Miscellaneous Devices") (part "Res1"))
    )
    (comp (ref "R24")
      (value "10K")
      (footprint "RESC1608X55X25ML10T15")
      (description "Chip Resistor, 10 KOhm, +/- 1%, 01 W, -55 to 155 degC, 0603 (1608 Metric), RoHS, Tape and Reel")
      (fields (field (name "MANUFACTURER") "Yageo") (field (name "TOLERANCE") "1%"))
      (libsource (lib "Altium Content Vault") (part "RES-2"))
    )
    (comp (ref "R25")
      (value "10K")
      (footprint "RESC1608X55X25ML10T15")
      (description "Chip Resistor, 10 KOhm, +/- 1%, 01 W, -55 to 155 degC, 0603 (1608 Metric), RoHS, Tape and Reel")
      (fields (field (name "MANUFACTURER") "Yageo") (field (name "TOLERANCE") "1%"))
      (libsource (lib "Altium Content Vault") (part "RES-2"))
    )
    (comp (ref "R26")
      (value "330")
      (footprint "RESC3116X65X40LL10T20")
      (description "Chip Resistor, 330 Ohm, +/- 1%, 250 mW, -55 to 155 degC, 1206 (3216 Metric), RoHS, Tape and Reel")
      (fields (field (name "MANUFACTURER") "Yageo") (field (name "TOLERANCE") "1%"))
      (libsource (lib "Altium Content Vault") (part "RES-2"))
    )
    (comp (ref "R27")
      (value "330")
      (footprint "RESC3116X65X40LL10T20")
      (description "Chip Resistor, 330 Ohm, +/- 1%, 250 mW, -55 to 155 degC, 1206 (3216 Metric), RoHS, Tape and Reel")
      (fields (field (name "MANUFACTURER") "Yageo") (field (name "TOLERANCE") "1%"))
      (libsource (lib "Altium Content Vault") (part "RES-2"))
    )
    (comp (ref "R28")
      (value "10K")
      (footprint "RESC1608X55X25ML10T15")
      (description "Chip Resistor, 10 KOhm, +/- 1%, 01 W, -55 to 155 degC, 0603 (1608 Metric), RoHS, Tape and Reel")
      (fields (field (name "MANUFACTURER") "Yageo") (field (name "TOLERANCE") "1%"))
      (libsource (lib "Altium Content Vault") (part "RES-2"))
    )
    (comp (ref "R29")
      (value "10K")
      (footprint "RESC1608X55X25ML10T15")
      (description "Chip Resistor, 10 KOhm, +/- 1%, 01 W, -55 to 155 degC, 0603 (1608 Metric), RoHS, Tape and Reel")
      (fields (field (name "MANUFACTURER") "Yageo") (field (name "TOLERANCE") "1%"))
      (libsource (lib "Altium Content Vault") (part "RES-2"))
    )
    (comp (ref "R30")
      (value "Res1")
      (footprint "AXIAL-0.3")
      (description "Resistor")
      (fields (field (name "ALTIUM_VALUE") "4.7K") (field (name "PUBLISHER") "Altium Limited"))
      (libsource (lib "Miscellaneous Devices") (part "Res1"))
    )
    (comp (ref "R31")
      (value "Res1")
      (footprint "AXIAL-0.3")
      (description "Resistor")
      (fields (field (name "ALTIUM_VALUE") "4.7K") (field (name "PUBLISHER") "Altium Limited"))
      (libsource (lib "Miscellaneous Devices") (part "Res1"))
    )
    (comp (ref "R32")
      (value "330")
      (footprint "RESC3116X65X40LL10T20")
      (description "Chip Resistor, 330 Ohm, +/- 1%, 250 mW, -55 to 155 degC, 1206 (3216 Metric), RoHS, Tape and Reel")
      (fields (field (name "MANUFACTURER") "Yageo") (field (name "TOLERANCE") "1%"))
      (libsource (lib "Altium Content Vault") (part "RES-2"))
    )
    (comp (ref "R33")
      (value "330")
      (footprint "RESC3116X65X40LL10T20")
      (description "Chip Resistor, 330 Ohm, +/- 1%, 250 mW, -55 to 155 degC, 1206 (3216 Metric), RoHS, Tape and Reel")
      (fields (field (name "MANUFACTURER") "Yageo") (field (name "TOLERANCE") "1%"))
      (libsource (lib "Altium Content Vault") (part "RES-2"))
    )
    (comp (ref "R34")
      (value "330")
      (footprint "RESC3116X65X40LL10T20")
      (description "Chip Resistor, 330 Ohm, +/- 1%, 250 mW, -55 to 155 degC, 1206 (3216 Metric), RoHS, Tape and Reel")
      (fields (field (name "MANUFACTURER") "Yageo") (field (name "TOLERANCE") "1%"))
      (libsource (lib "Altium Content Vault") (part "RES-2"))
    )
    (comp (ref "R35")
      (value "330")
      (footprint "RESC3116X65X40LL10T20")
      (description "Chip Resistor, 330 Ohm, +/- 1%, 250 mW, -55 to 155 degC, 1206 (3216 Metric), RoHS, Tape and Reel")
      (fields (field (name "MANUFACTURER") "Yageo") (field (name "TOLERANCE") "1%"))
      (libsource (lib "Altium Content Vault") (part "RES-2"))
    )
    (comp (ref "U1")
      (value "NE555DR")
      (footprint "D0008A_L")
      (libsource (lib "Altium Content Vault") (part "CMP-1685-00007-1"))
    )
    (comp (ref "U2")
      (value "NE555DR")
      (footprint "D0008A_L")
      (libsource (lib "Altium Content Vault") (part "CMP-1685-00007-1"))
    )
    (comp (ref "U3")
      (value "NE555DR")
      (footprint "D0008A_L")
      (libsource (lib "Altium Content Vault") (part "CMP-1685-00007-1"))
    )
    (comp (ref "U4")
      (value "NE555DR")
      (footprint "D0008A_L")
      (libsource (lib "Altium Content Vault") (part "CMP-1685-00007-1"))
    )
    (comp (ref "U5")
      (value "NE555DR")
      (footprint "D0008A_L")
      (libsource (lib "Altium Content Vault") (part "CMP-1685-00007-1"))
    )
  )
  (nets
    (net (code "1") (name "/+ Valve 1") (class "Default")
      (node (ref "D2") (pin "2") (pinfunction "K_2") (pintype "passive"))
      (node (ref "D3") (pin "2") (pinfunction "K_2") (pintype "passive"))
      (node (ref "P1") (pin "1") (pinfunction "1_1") (pintype "passive"))
      (node (ref "Q2") (pin "4") (pinfunction "C_4") (pintype "passive"))
    )
    (net (code "2") (name "/+ Valve 2") (class "Default")
      (node (ref "D7") (pin "2") (pinfunction "K_2") (pintype "passive"))
      (node (ref "D8") (pin "2") (pinfunction "K_2") (pintype "passive"))
      (node (ref "P2") (pin "1") (pinfunction "1_1") (pintype "passive"))
      (node (ref "Q7") (pin "4") (pinfunction "C_4") (pintype "passive"))
    )
    (net (code "3") (name "/+ Valve 3") (class "Default")
      (node (ref "D11") (pin "2") (pinfunction "K_2") (pintype "passive"))
      (node (ref "D9") (pin "2") (pinfunction "K_2") (pintype "passive"))
      (node (ref "P3") (pin "1") (pinfunction "1_1") (pintype "passive"))
      (node (ref "Q8") (pin "4") (pinfunction "C_4") (pintype "passive"))
    )
    (net (code "4") (name "/+ Valve 4") (class "Default")
      (node (ref "D15") (pin "2") (pinfunction "K_2") (pintype "passive"))
      (node (ref "D17") (pin "2") (pinfunction "K_2") (pintype "passive"))
      (node (ref "P5") (pin "1") (pinfunction "1_1") (pintype "passive"))
      (node (ref "Q15") (pin "4") (pinfunction "C_4") (pintype "passive"))
    )
    (net (code "5") (name "/+ Valve 5") (class "Default")
      (node (ref "D16") (pin "2") (pinfunction "K_2") (pintype "passive"))
      (node (ref "D18") (pin "2") (pinfunction "K_2") (pintype "passive"))
      (node (ref "P4") (pin "1") (pinfunction "1_1") (pintype "passive"))
      (node (ref "Q16") (pin "4") (pinfunction "C_4") (pintype "passive"))
    )
    (net (code "6") (name "/- Valve 1") (class "Default")
      (node (ref "D4") (pin "2") (pinfunction "K_2") (pintype "passive"))
      (node (ref "P1") (pin "2") (pinfunction "2_2") (pintype "passive"))
      (node (ref "Q4") (pin "4") (pinfunction "C_4") (pintype "passive"))
    )
    (net (code "7") (name "/- Valve 2") (class "Default")
      (node (ref "D10") (pin "2") (pinfunction "K_2") (pintype "passive"))
      (node (ref "P2") (pin "2") (pinfunction "2_2") (pintype "passive"))
      (node (ref "Q10") (pin "4") (pinfunction "C_4") (pintype "passive"))
    )
    (net (code "8") (name "/- Valve 3") (class "Default")
      (node (ref "D12") (pin "2") (pinfunction "K_2") (pintype "passive"))
      (node (ref "P3") (pin "2") (pinfunction "2_2") (pintype "passive"))
      (node (ref "Q12") (pin "4") (pinfunction "C_4") (pintype "passive"))
    )
    (net (code "9") (name "/- Valve 4") (class "Default")
      (node (ref "D19") (pin "2") (pinfunction "K_2") (pintype "passive"))
      (node (ref "P5") (pin "2") (pinfunction "2_2") (pintype "passive"))
      (node (ref "Q19") (pin "4") (pinfunction "C_4") (pintype "passive"))
    )
    (net (code "10") (name "/- Valve 5") (class "Default")
      (node (ref "D20") (pin "2") (pinfunction "K_2") (pintype "passive"))
      (node (ref "P4") (pin "2") (pinfunction "2_2") (pintype "passive"))
      (node (ref "Q20") (pin "4") (pinfunction "C_4") (pintype "passive"))
    )
    (net (code "11") (name "/Signal + 1") (class "Default")
      (node (ref "C1") (pin "1") (pinfunction "1_1") (pintype "passive"))
      (node (ref "PC-1") (pin "H1_3") (pinfunction "H1_3_H1_3") (pintype "passive"))
      (node (ref "R6") (pin "2") (pinfunction "2_2") (pintype "passive"))
    )
    (net (code "12") (name "/Signal + 2") (class "Default")
      (node (ref "C4") (pin "1") (pinfunction "1_1") (pintype "passive"))
      (node (ref "R16") (pin "2") (pinfunction "2_2") (pintype "passive"))
    )
    (net (code "13") (name "/Signal + 3") (class "Default")
      (node (ref "C7") (pin "1") (pinfunction "1_1") (pintype "passive"))
      (node (ref "PC-1") (pin "H1_5") (pinfunction "H1_5_H1_5") (pintype "passive"))
      (node (ref "R20") (pin "2") (pinfunction "2_2") (pintype "passive"))
    )
    (net (code "14") (name "/Signal + 4") (class "Default")
      (node (ref "C10") (pin "1") (pinfunction "1_1") (pintype "passive"))
      (node (ref "R32") (pin "2") (pinfunction "2_2") (pintype "passive"))
    )
    (net (code "15") (name "/Signal + 5") (class "Default")
      (node (ref "C11") (pin "1") (pinfunction "1_1") (pintype "passive"))
      (node (ref "PC-1") (pin "H1_7") (pinfunction "H1_7_H1_7") (pintype "passive"))
      (node (ref "R33") (pin "2") (pinfunction "2_2") (pintype "passive"))
    )
    (net (code "16") (name "/V1") (class "Default")
      (node (ref "PC-1") (pin "H1_21") (pinfunction "H1_21_H1_21") (pintype "passive"))
      (node (ref "Q15") (pin "3") (pinfunction "E_3") (pintype "passive"))
      (node (ref "Q16") (pin "3") (pinfunction "E_3") (pintype "passive"))
      (node (ref "Q2") (pin "3") (pinfunction "E_3") (pintype "passive"))
      (node (ref "Q7") (pin "3") (pinfunction "E_3") (pintype "passive"))
      (node (ref "Q8") (pin "3") (pinfunction "E_3") (pintype "passive"))
      (node (ref "R14") (pin "1") (pinfunction "1_1") (pintype "passive"))
      (node (ref "R18") (pin "1") (pinfunction "1_1") (pintype "passive"))
      (node (ref "R28") (pin "2") (pinfunction "2_2") (pintype "passive"))
      (node (ref "R29") (pin "2") (pinfunction "2_2") (pintype "passive"))
      (node (ref "R4") (pin "2") (pinfunction "2_2") (pintype "passive"))
    )
    (net (code "17") (name "/V2") (class "Default")
      (node (ref "D15") (pin "1") (pinfunction "A_1") (pintype "passive"))
      (node (ref "D16") (pin "1") (pinfunction "A_1") (pintype "passive"))
      (node (ref "D2") (pin "1") (pinfunction "A_1") (pintype "passive"))
      (node (ref "D7") (pin "1") (pinfunction "A_1") (pintype "passive"))
      (node (ref "D9") (pin "1") (pinfunction "A_1") (pintype "passive"))
      (node (ref "PC-1") (pin "H1_52") (pinfunction "H1_52_H1_52") (pintype "passive"))
    )
    (net (code "18") (name "/Vcc") (class "Default")
      (node (ref "PC-1") (pin "H1_51") (pinfunction "H1_51_H1_51") (pintype "passive"))
      (node (ref "R1") (pin "1") (pinfunction "1_1") (pintype "passive"))
      (node (ref "R10") (pin "1") (pinfunction "1_1") (pintype "passive"))
      (node (ref "R11") (pin "1") (pinfunction "1_1") (pintype "passive"))
      (node (ref "R2") (pin "1") (pinfunction "1_1") (pintype "passive"))
      (node (ref "R22") (pin "1") (pinfunction "1_1") (pintype "passive"))
      (node (ref "R23") (pin "1") (pinfunction "1_1") (pintype "passive"))
      (node (ref "R24") (pin "1") (pinfunction "1_1") (pintype "passive"))
      (node (ref "R25") (pin "1") (pinfunction "1_1") (pintype "passive"))
      (node (ref "R8") (pin "1") (pinfunction "1_1") (pintype "passive"))
      (node (ref "R9") (pin "2") (pinfunction "2_2") (pintype "passive"))
      (node (ref "U1") (pin "4") (pinfunction "~{RESET}_4") (pintype "input"))
      (node (ref "U1") (pin "8") (pinfunction "VCC_8") (pintype "power_in"))
      (node (ref "U2") (pin "4") (pinfunction "~{RESET}_4") (pintype "input"))
      (node (ref "U2") (pin "8") (pinfunction "VCC_8") (pintype "power_in"))
      (node (ref "U3") (pin "4") (pinfunction "~{RESET}_4") (pintype "input"))
      (node (ref "U3") (pin "8") (pinfunction "VCC_8") (pintype "power_in"))
      (node (ref "U4") (pin "4") (pinfunction "~{RESET}_4") (pintype "input"))
      (node (ref "U4") (pin "8") (pinfunction "VCC_8") (pintype "power_in"))
      (node (ref "U5") (pin "4") (pinfunction "~{RESET}_4") (pintype "input"))
      (node (ref "U5") (pin "8") (pinfunction "VCC_8") (pintype "power_in"))
    )
    (net (code "19") (name "GND") (class "Default")
      (node (ref "C12") (pin "1") (pinfunction "1_1") (pintype "passive"))
      (node (ref "C13") (pin "1") (pinfunction "1_1") (pintype "passive"))
      (node (ref "C14") (pin "1") (pinfunction "1_1") (pintype "passive"))
      (node (ref "C15") (pin "1") (pinfunction "1_1") (pintype "passive"))
      (node (ref "C2") (pin "1") (pinfunction "1_1") (pintype "passive"))
      (node (ref "C3") (pin "1") (pinfunction "1_1") (pintype "passive"))
      (node (ref "C5") (pin "1") (pinfunction "1_1") (pintype "passive"))
      (node (ref "C6") (pin "1") (pinfunction "1_1") (pintype "passive"))
      (node (ref "C8") (pin "1") (pinfunction "1_1") (pintype "passive"))
      (node (ref "D1") (pin "1") (pinfunction "A_1") (pintype "passive"))
      (node (ref "D13") (pin "1") (pinfunction "A_1") (pintype "passive"))
      (node (ref "D14") (pin "1") (pinfunction "A_1") (pintype "passive"))
      (node (ref "D5") (pin "1") (pinfunction "A_1") (pintype "passive"))
      (node (ref "D6") (pin "1") (pinfunction "A_1") (pintype "passive"))
      (node (ref "PC-1") (pin "H2_29") (pinfunction "H2_29_H2_29") (pintype "passive"))
      (node (ref "Q1") (pin "2") (pinfunction "E_2") (pintype "passive"))
      (node (ref "Q10") (pin "3") (pinfunction "E_3") (pintype "passive"))
      (node (ref "Q11") (pin "2") (pinfunction "E_2") (pintype "passive"))
      (node (ref "Q12") (pin "3") (pinfunction "E_3") (pintype "passive"))
      (node (ref "Q13") (pin "2") (pinfunction "E_2") (pintype "passive"))
      (node (ref "Q14") (pin "2") (pinfunction "E_2") (pintype "passive"))
      (node (ref "Q17") (pin "2") (pinfunction "E_2") (pintype "passive"))
      (node (ref "Q18") (pin "2") (pinfunction "E_2") (pintype "passive"))
      (node (ref "Q19") (pin "3") (pinfunction "E_3") (pintype "passive"))
      (node (ref "Q20") (pin "3") (pinfunction "E_3") (pintype "passive"))
      (node (ref "Q3") (pin "2") (pinfunction "E_2") (pintype "passive"))
      (node (ref "Q4") (pin "3") (pinfunction "E_3") (pintype "passive"))
      (node (ref "Q5") (pin "2") (pinfunction "E_2") (pintype "passive"))
      (node (ref "Q6") (pin "2") (pinfunction "E_2") (pintype "passive"))
      (node (ref "Q9") (pin "2") (pinfunction "E_2") (pintype "passive"))
      (node (ref "U1") (pin "1") (pinfunction "GND_1") (pintype "output"))
      (node (ref "U2") (pin "1") (pinfunction "GND_1") (pintype "output"))
      (node (ref "U3") (pin "1") (pinfunction "GND_1") (pintype "output"))
      (node (ref "U4") (pin "1") (pinfunction "GND_1") (pintype "output"))
      (node (ref "U5") (pin "1") (pinfunction "GND_1") (pintype "output"))
    )
    (net (code "20") (name "Net-(C1-Pad2)") (class "Default")
      (node (ref "C1") (pin "2") (pinfunction "2_2") (pintype "passive"))
      (node (ref "R3") (pin "1") (pinfunction "1_1") (pintype "passive"))
    )
    (net (code "21") (name "Net-(C4-Pad2)") (class "Default")
      (node (ref "C4") (pin "2") (pinfunction "2_2") (pintype "passive"))
      (node (ref "R12") (pin "1") (pinfunction "1_1") (pintype "passive"))
    )
    (net (code "22") (name "Net-(C7-Pad2)") (class "Default")
      (node (ref "C7") (pin "2") (pinfunction "2_2") (pintype "passive"))
      (node (ref "R13") (pin "1") (pinfunction "1_1") (pintype "passive"))
    )
    (net (code "23") (name "Net-(C10-Pad2)") (class "Default")
      (node (ref "C10") (pin "2") (pinfunction "2_2") (pintype "passive"))
      (node (ref "R26") (pin "1") (pinfunction "1_1") (pintype "passive"))
    )
    (net (code "24") (name "Net-(C11-Pad2)") (class "Default")
      (node (ref "C11") (pin "2") (pinfunction "2_2") (pintype "passive"))
      (node (ref "R27") (pin "1") (pinfunction "1_1") (pintype "passive"))
    )
    (net (code "25") (name "Net-(D1-K)") (class "Default")
      (node (ref "D1") (pin "2") (pinfunction "K_2") (pintype "passive"))
      (node (ref "Q1") (pin "1") (pinfunction "B_1") (pintype "passive"))
      (node (ref "R3") (pin "2") (pinfunction "2_2") (pintype "passive"))
    )
    (net (code "26") (name "Net-(D3-A)") (class "Default")
      (node (ref "D3") (pin "1") (pinfunction "A_1") (pintype "passive"))
      (node (ref "D4") (pin "1") (pinfunction "A_1") (pintype "passive"))
    )
    (net (code "27") (name "Net-(D5-K)") (class "Default")
      (node (ref "D5") (pin "2") (pinfunction "K_2") (pintype "passive"))
      (node (ref "Q5") (pin "1") (pinfunction "B_1") (pintype "passive"))
      (node (ref "R12") (pin "2") (pinfunction "2_2") (pintype "passive"))
    )
    (net (code "28") (name "Net-(D6-K)") (class "Default")
      (node (ref "D6") (pin "2") (pinfunction "K_2") (pintype "passive"))
      (node (ref "Q6") (pin "1") (pinfunction "B_1") (pintype "passive"))
      (node (ref "R13") (pin "2") (pinfunction "2_2") (pintype "passive"))
    )
    (net (code "29") (name "Net-(D10-A)") (class "Default")
      (node (ref "D10") (pin "1") (pinfunction "A_1") (pintype "passive"))
      (node (ref "D8") (pin "1") (pinfunction "A_1") (pintype "passive"))
    )
    (net (code "30") (name "Net-(D11-A)") (class "Default")
      (node (ref "D11") (pin "1") (pinfunction "A_1") (pintype "passive"))
      (node (ref "D12") (pin "1") (pinfunction "A_1") (pintype "passive"))
    )
    (net (code "31") (name "Net-(D13-K)") (class "Default")
      (node (ref "D13") (pin "2") (pinfunction "K_2") (pintype "passive"))
      (node (ref "Q13") (pin "1") (pinfunction "B_1") (pintype "passive"))
      (node (ref "R26") (pin "2") (pinfunction "2_2") (pintype "passive"))
    )
    (net (code "32") (name "Net-(D14-K)") (class "Default")
      (node (ref "D14") (pin "2") (pinfunction "K_2") (pintype "passive"))
      (node (ref "Q14") (pin "1") (pinfunction "B_1") (pintype "passive"))
      (node (ref "R27") (pin "2") (pinfunction "2_2") (pintype "passive"))
    )
    (net (code "33") (name "Net-(D17-A)") (class "Default")
      (node (ref "D17") (pin "1") (pinfunction "A_1") (pintype "passive"))
      (node (ref "D19") (pin "1") (pinfunction "A_1") (pintype "passive"))
    )
    (net (code "34") (name "Net-(D18-A)") (class "Default")
      (node (ref "D18") (pin "1") (pinfunction "A_1") (pintype "passive"))
      (node (ref "D20") (pin "1") (pinfunction "A_1") (pintype "passive"))
    )
    (net (code "35") (name "Net-(Q1-C)") (class "Default")
      (node (ref "Q1") (pin "3") (pinfunction "C_3") (pintype "passive"))
      (node (ref "R2") (pin "2") (pinfunction "2_2") (pintype "passive"))
      (node (ref "U1") (pin "2") (pinfunction "TRIG_2") (pintype "input"))
    )
    (net (code "36") (name "Net-(Q2-B)") (class "Default")
      (node (ref "Q2") (pin "1") (pinfunction "B_1") (pintype "passive"))
      (node (ref "R5") (pin "2") (pinfunction "2_2") (pintype "passive"))
    )
    (net (code "37") (name "Net-(Q3-B)") (class "Default")
      (node (ref "Q3") (pin "1") (pinfunction "B_1") (pintype "passive"))
      (node (ref "R7") (pin "1") (pinfunction "1_1") (pintype "passive"))
    )
    (net (code "38") (name "Net-(Q3-C)") (class "Default")
      (node (ref "Q3") (pin "3") (pinfunction "C_3") (pintype "passive"))
      (node (ref "R4") (pin "1") (pinfunction "1_1") (pintype "passive"))
      (node (ref "R5") (pin "1") (pinfunction "1_1") (pintype "passive"))
    )
    (net (code "39") (name "Net-(Q4-B)") (class "Default")
      (node (ref "Q4") (pin "1") (pinfunction "B_1") (pintype "passive"))
      (node (ref "R6") (pin "1") (pinfunction "1_1") (pintype "passive"))
    )
    (net (code "40") (name "Net-(Q5-C)") (class "Default")
      (node (ref "Q5") (pin "3") (pinfunction "C_3") (pintype "passive"))
      (node (ref "R9") (pin "1") (pinfunction "1_1") (pintype "passive"))
      (node (ref "U2") (pin "2") (pinfunction "TRIG_2") (pintype "input"))
    )
    (net (code "41") (name "Net-(Q6-C)") (class "Default")
      (node (ref "Q6") (pin "3") (pinfunction "C_3") (pintype "passive"))
      (node (ref "R11") (pin "2") (pinfunction "2_2") (pintype "passive"))
      (node (ref "U3") (pin "2") (pinfunction "TRIG_2") (pintype "input"))
    )
    (net (code "42") (name "Net-(Q7-B)") (class "Default")
      (node (ref "Q7") (pin "1") (pinfunction "B_1") (pintype "passive"))
      (node (ref "R15") (pin "2") (pinfunction "2_2") (pintype "passive"))
    )
    (net (code "43") (name "Net-(Q8-B)") (class "Default")
      (node (ref "Q8") (pin "1") (pinfunction "B_1") (pintype "passive"))
      (node (ref "R19") (pin "2") (pinfunction "2_2") (pintype "passive"))
    )
    (net (code "44") (name "Net-(Q9-B)") (class "Default")
      (node (ref "Q9") (pin "1") (pinfunction "B_1") (pintype "passive"))
      (node (ref "R17") (pin "1") (pinfunction "1_1") (pintype "passive"))
    )
    (net (code "45") (name "Net-(Q9-C)") (class "Default")
      (node (ref "Q9") (pin "3") (pinfunction "C_3") (pintype "passive"))
      (node (ref "R14") (pin "2") (pinfunction "2_2") (pintype "passive"))
      (node (ref "R15") (pin "1") (pinfunction "1_1") (pintype "passive"))
    )
    (net (code "46") (name "Net-(Q10-B)") (class "Default")
      (node (ref "Q10") (pin "1") (pinfunction "B_1") (pintype "passive"))
      (node (ref "R16") (pin "1") (pinfunction "1_1") (pintype "passive"))
    )
    (net (code "47") (name "Net-(Q11-B)") (class "Default")
      (node (ref "Q11") (pin "1") (pinfunction "B_1") (pintype "passive"))
      (node (ref "R21") (pin "1") (pinfunction "1_1") (pintype "passive"))
    )
    (net (code "48") (name "Net-(Q11-C)") (class "Default")
      (node (ref "Q11") (pin "3") (pinfunction "C_3") (pintype "passive"))
      (node (ref "R18") (pin "2") (pinfunction "2_2") (pintype "passive"))
      (node (ref "R19") (pin "1") (pinfunction "1_1") (pintype "passive"))
    )
    (net (code "49") (name "Net-(Q12-B)") (class "Default")
      (node (ref "Q12") (pin "1") (pinfunction "B_1") (pintype "passive"))
      (node (ref "R20") (pin "1") (pinfunction "1_1") (pintype "passive"))
    )
    (net (code "50") (name "Net-(Q13-C)") (class "Default")
      (node (ref "Q13") (pin "3") (pinfunction "C_3") (pintype "passive"))
      (node (ref "R24") (pin "2") (pinfunction "2_2") (pintype "passive"))
      (node (ref "U4") (pin "2") (pinfunction "TRIG_2") (pintype "input"))
    )
    (net (code "51") (name "Net-(Q14-C)") (class "Default")
      (node (ref "Q14") (pin "3") (pinfunction "C_3") (pintype "passive"))
      (node (ref "R25") (pin "2") (pinfunction "2_2") (pintype "passive"))
      (node (ref "U5") (pin "2") (pinfunction "TRIG_2") (pintype "input"))
    )
    (net (code "52") (name "Net-(Q15-B)") (class "Default")
      (node (ref "Q15") (pin "1") (pinfunction "B_1") (pintype "passive"))
      (node (ref "R30") (pin "2") (pinfunction "2_2") (pintype "passive"))
    )
    (net (code "53") (name "Net-(Q16-B)") (class "Default")
      (node (ref "Q16") (pin "1") (pinfunction "B_1") (pintype "passive"))
      (node (ref "R31") (pin "2") (pinfunction "2_2") (pintype "passive"))
    )
    (net (code "54") (name "Net-(Q17-B)") (class "Default")
      (node (ref "Q17") (pin "1") (pinfunction "B_1") (pintype "passive"))
      (node (ref "R34") (pin "1") (pinfunction "1_1") (pintype "passive"))
    )
    (net (code "55") (name "Net-(Q17-C)") (class "Default")
      (node (ref "Q17") (pin "3") (pinfunction "C_3") (pintype "passive"))
      (node (ref "R28") (pin "1") (pinfunction "1_1") (pintype "passive"))
      (node (ref "R30") (pin "1") (pinfunction "1_1") (pintype "passive"))
    )
    (net (code "56") (name "Net-(Q18-B)") (class "Default")
      (node (ref "Q18") (pin "1") (pinfunction "B_1") (pintype "passive"))
      (node (ref "R35") (pin "1") (pinfunction "1_1") (pintype "passive"))
    )
    (net (code "57") (name "Net-(Q18-C)") (class "Default")
      (node (ref "Q18") (pin "3") (pinfunction "C_3") (pintype "passive"))
      (node (ref "R29") (pin "1") (pinfunction "1_1") (pintype "passive"))
      (node (ref "R31") (pin "1") (pinfunction "1_1") (pintype "passive"))
    )
    (net (code "58") (name "Net-(Q19-B)") (class "Default")
      (node (ref "Q19") (pin "1") (pinfunction "B_1") (pintype "passive"))
      (node (ref "R32") (pin "1") (pinfunction "1_1") (pintype "passive"))
    )
    (net (code "59") (name "Net-(Q20-B)") (class "Default")
      (node (ref "Q20") (pin "1") (pinfunction "B_1") (pintype "passive"))
      (node (ref "R33") (pin "1") (pinfunction "1_1") (pintype "passive"))
    )
    (net (code "60") (name "Net-(U1-CONT)") (class "Default")
      (node (ref "C2") (pin "2") (pinfunction "2_2") (pintype "passive"))
      (node (ref "U1") (pin "5") (pinfunction "CONT_5") (pintype "bidirectional"))
    )
    (net (code "61") (name "Net-(U1-DISCH)") (class "Default")
      (node (ref "C3") (pin "2") (pinfunction "2_2") (pintype "passive"))
      (node (ref "R1") (pin "2") (pinfunction "2_2") (pintype "passive"))
      (node (ref "U1") (pin "6") (pinfunction "THRES_6") (pintype "input"))
      (node (ref "U1") (pin "7") (pinfunction "DISCH_7") (pintype "open_collector"))
    )
    (net (code "62") (name "Net-(U1-OUT)") (class "Default")
      (node (ref "R7") (pin "2") (pinfunction "2_2") (pintype "passive"))
      (node (ref "U1") (pin "3") (pinfunction "OUT_3") (pintype "output"))
    )
    (net (code "63") (name "Net-(U2-CONT)") (class "Default")
      (node (ref "C5") (pin "2") (pinfunction "2_2") (pintype "passive"))
      (node (ref "U2") (pin "5") (pinfunction "CONT_5") (pintype "bidirectional"))
    )
    (net (code "64") (name "Net-(U2-DISCH)") (class "Default")
      (node (ref "C6") (pin "2") (pinfunction "2_2") (pintype "passive"))
      (node (ref "R8") (pin "2") (pinfunction "2_2") (pintype "passive"))
      (node (ref "U2") (pin "6") (pinfunction "THRES_6") (pintype "input"))
      (node (ref "U2") (pin "7") (pinfunction "DISCH_7") (pintype "open_collector"))
    )
    (net (code "65") (name "Net-(U2-OUT)") (class "Default")
      (node (ref "R17") (pin "2") (pinfunction "2_2") (pintype "passive"))
      (node (ref "U2") (pin "3") (pinfunction "OUT_3") (pintype "output"))
    )
    (net (code "66") (name "Net-(U3-CONT)") (class "Default")
      (node (ref "C8") (pin "2") (pinfunction "2_2") (pintype "passive"))
      (node (ref "U3") (pin "5") (pinfunction "CONT_5") (pintype "bidirectional"))
    )
    (net (code "67") (name "Net-(U3-DISCH)") (class "Default")
      (node (ref "C9") (pin "2") (pinfunction "2_2") (pintype "passive"))
      (node (ref "R10") (pin "2") (pinfunction "2_2") (pintype "passive"))
      (node (ref "U3") (pin "6") (pinfunction "THRES_6") (pintype "input"))
      (node (ref "U3") (pin "7") (pinfunction "DISCH_7") (pintype "open_collector"))
    )
    (net (code "68") (name "Net-(U3-OUT)") (class "Default")
      (node (ref "R21") (pin "2") (pinfunction "2_2") (pintype "passive"))
      (node (ref "U3") (pin "3") (pinfunction "OUT_3") (pintype "output"))
    )
    (net (code "69") (name "Net-(U4-CONT)") (class "Default")
      (node (ref "C12") (pin "2") (pinfunction "2_2") (pintype "passive"))
      (node (ref "U4") (pin "5") (pinfunction "CONT_5") (pintype "bidirectional"))
    )
    (net (code "70") (name "Net-(U4-DISCH)") (class "Default")
      (node (ref "C14") (pin "2") (pinfunction "2_2") (pintype "passive"))
      (node (ref "R22") (pin "2") (pinfunction "2_2") (pintype "passive"))
      (node (ref "U4") (pin "6") (pinfunction "THRES_6") (pintype "input"))
      (node (ref "U4") (pin "7") (pinfunction "DISCH_7") (pintype "open_collector"))
    )
    (net (code "71") (name "Net-(U4-OUT)") (class "Default")
      (node (ref "R34") (pin "2") (pinfunction "2_2") (pintype "passive"))
      (node (ref "U4") (pin "3") (pinfunction "OUT_3") (pintype "output"))
    )
    (net (code "72") (name "Net-(U5-CONT)") (class "Default")
      (node (ref "C13") (pin "2") (pinfunction "2_2") (pintype "passive"))
      (node (ref "U5") (pin "5") (pinfunction "CONT_5") (pintype "bidirectional"))
    )
    (net (code "73") (name "Net-(U5-DISCH)") (class "Default")
      (node (ref "C15") (pin "2") (pinfunction "2_2") (pintype "passive"))
      (node (ref "R23") (pin "2") (pinfunction "2_2") (pintype "passive"))
      (node (ref "U5") (pin "6") (pinfunction "THRES_6") (pintype "input"))
      (node (ref "U5") (pin "7") (pinfunction "DISCH_7") (pintype "open_collector"))
    )
    (net (code "74") (name "Net-(U5-OUT)") (class "Default")
      (node (ref "R35") (pin "2") (pinfunction "2_2") (pintype "passive"))
      (node (ref "U5") (pin "3") (pinfunction "OUT_3") (pintype "output"))
    )
    (net (code "75") (name "unconnected-(C9-Pad1)") (class "Default")
      (node (ref "C9") (pin "1") (pinfunction "1_1") (pintype "passive"))
    )
    (net (code "76") (name "unconnected-(P1-PadMP1)") (class "Default")
      (node (ref "P1") (pin "MP1") (pinfunction "MP1_MP1") (pintype "passive"))
    )
    (net (code "77") (name "unconnected-(P1-PadMP2)") (class "Default")
      (node (ref "P1") (pin "MP2") (pinfunction "MP2_MP2") (pintype "passive"))
    )
    (net (code "78") (name "unconnected-(P2-PadMP1)") (class "Default")
      (node (ref "P2") (pin "MP1") (pinfunction "MP1_MP1") (pintype "passive"))
    )
    (net (code "79") (name "unconnected-(P2-PadMP2)") (class "Default")
      (node (ref "P2") (pin "MP2") (pinfunction "MP2_MP2") (pintype "passive"))
    )
    (net (code "80") (name "unconnected-(P3-PadMP1)") (class "Default")
      (node (ref "P3") (pin "MP1") (pinfunction "MP1_MP1") (pintype "passive"))
    )
    (net (code "81") (name "unconnected-(P3-PadMP2)") (class "Default")
      (node (ref "P3") (pin "MP2") (pinfunction "MP2_MP2") (pintype "passive"))
    )
    (net (code "82") (name "unconnected-(P4-PadMP1)") (class "Default")
      (node (ref "P4") (pin "MP1") (pinfunction "MP1_MP1") (pintype "passive"))
    )
    (net (code "83") (name "unconnected-(P4-PadMP2)") (class "Default")
      (node (ref "P4") (pin "MP2") (pinfunction "MP2_MP2") (pintype "passive"))
    )
    (net (code "84") (name "unconnected-(P5-PadMP1)") (class "Default")
      (node (ref "P5") (pin "MP1") (pinfunction "MP1_MP1") (pintype "passive"))
    )
    (net (code "85") (name "unconnected-(P5-PadMP2)") (class "Default")
      (node (ref "P5") (pin "MP2") (pinfunction "MP2_MP2") (pintype "passive"))
    )
    (net (code "86") (name "unconnected-(PC-1-PadH1_1)") (class "Default")
      (node (ref "PC-1") (pin "H1_1") (pinfunction "H1_1_H1_1") (pintype "passive"))
    )
    (net (code "87") (name "unconnected-(PC-1-PadH1_2)") (class "Default")
      (node (ref "PC-1") (pin "H1_2") (pinfunction "H1_2_H1_2") (pintype "passive"))
    )
    (net (code "88") (name "unconnected-(PC-1-PadH1_4)") (class "Default")
      (node (ref "PC-1") (pin "H1_4") (pinfunction "H1_4_H1_4") (pintype "passive"))
    )
    (net (code "89") (name "unconnected-(PC-1-PadH1_6)") (class "Default")
      (node (ref "PC-1") (pin "H1_6") (pinfunction "H1_6_H1_6") (pintype "passive"))
    )
    (net (code "90") (name "unconnected-(PC-1-PadH1_8)") (class "Default")
      (node (ref "PC-1") (pin "H1_8") (pinfunction "H1_8_H1_8") (pintype "passive"))
    )
    (net (code "91") (name "unconnected-(PC-1-PadH1_9)") (class "Default")
      (node (ref "PC-1") (pin "H1_9") (pinfunction "H1_9_H1_9") (pintype "passive"))
    )
    (net (code "92") (name "unconnected-(PC-1-PadH1_10)") (class "Default")
      (node (ref "PC-1") (pin "H1_10") (pinfunction "H1_10_H1_10") (pintype "passive"))
    )
    (net (code "93") (name "unconnected-(PC-1-PadH1_11)") (class "Default")
      (node (ref "PC-1") (pin "H1_11") (pinfunction "H1_11_H1_11") (pintype "passive"))
    )
    (net (code "94") (name "unconnected-(PC-1-PadH1_12)") (class "Default")
      (node (ref "PC-1") (pin "H1_12") (pinfunction "H1_12_H1_12") (pintype "passive"))
    )
    (net (code "95") (name "unconnected-(PC-1-PadH1_13)") (class "Default")
      (node (ref "PC-1") (pin "H1_13") (pinfunction "H1_13_H1_13") (pintype "passive"))
    )
    (net (code "96") (name "unconnected-(PC-1-PadH1_14)") (class "Default")
      (node (ref "PC-1") (pin "H1_14") (pinfunction "H1_14_H1_14") (pintype "passive"))
    )
    (net (code "97") (name "unconnected-(PC-1-PadH1_15)") (class "Default")
      (node (ref "PC-1") (pin "H1_15") (pinfunction "H1_15_H1_15") (pintype "passive"))
    )
    (net (code "98") (name "unconnected-(PC-1-PadH1_16)") (class "Default")
      (node (ref "PC-1") (pin "H1_16") (pinfunction "H1_16_H1_16") (pintype "passive"))
    )
    (net (code "99") (name "unconnected-(PC-1-PadH1_17)") (class "Default")
      (node (ref "PC-1") (pin "H1_17") (pinfunction "H1_17_H1_17") (pintype "passive"))
    )
    (net (code "100") (name "unconnected-(PC-1-PadH1_18)") (class "Default")
      (node (ref "PC-1") (pin "H1_18") (pinfunction "H1_18_H1_18") (pintype "passive"))
    )
    (net (code "101") (name "unconnected-(PC-1-PadH1_19)") (class "Default")
      (node (ref "PC-1") (pin "H1_19") (pinfunction "H1_19_H1_19") (pintype "passive"))
    )
    (net (code "102") (name "unconnected-(PC-1-PadH1_20)") (class "Default")
      (node (ref "PC-1") (pin "H1_20") (pinfunction "H1_20_H1_20") (pintype "passive"))
    )
    (net (code "103") (name "unconnected-(PC-1-PadH1_22)") (class "Default")
      (node (ref "PC-1") (pin "H1_22") (pinfunction "H1_22_H1_22") (pintype "passive"))
    )
    (net (code "104") (name "unconnected-(PC-1-PadH1_23)") (class "Default")
      (node (ref "PC-1") (pin "H1_23") (pinfunction "H1_23_H1_23") (pintype "passive"))
    )
    (net (code "105") (name "unconnected-(PC-1-PadH1_24)") (class "Default")
      (node (ref "PC-1") (pin "H1_24") (pinfunction "H1_24_H1_24") (pintype "passive"))
    )
    (net (code "106") (name "unconnected-(PC-1-PadH1_25)") (class "Default")
      (node (ref "PC-1") (pin "H1_25") (pinfunction "H1_25_H1_25") (pintype "passive"))
    )
    (net (code "107") (name "unconnected-(PC-1-PadH1_26)") (class "Default")
      (node (ref "PC-1") (pin "H1_26") (pinfunction "H1_26_H1_26") (pintype "passive"))
    )
    (net (code "108") (name "unconnected-(PC-1-PadH1_27)") (class "Default")
      (node (ref "PC-1") (pin "H1_27") (pinfunction "H1_27_H1_27") (pintype "passive"))
    )
    (net (code "109") (name "unconnected-(PC-1-PadH1_28)") (class "Default")
      (node (ref "PC-1") (pin "H1_28") (pinfunction "H1_28_H1_28") (pintype "passive"))
    )
    (net (code "110") (name "unconnected-(PC-1-PadH1_29)") (class "Default")
      (node (ref "PC-1") (pin "H1_29") (pinfunction "H1_29_H1_29") (pintype "passive"))
    )
    (net (code "111") (name "unconnected-(PC-1-PadH1_30)") (class "Default")
      (node (ref "PC-1") (pin "H1_30") (pinfunction "H1_30_H1_30") (pintype "passive"))
    )
    (net (code "112") (name "unconnected-(PC-1-PadH1_31)") (class "Default")
      (node (ref "PC-1") (pin "H1_31") (pinfunction "H1_31_H1_31") (pintype "passive"))
    )
    (net (code "113") (name "unconnected-(PC-1-PadH1_32)") (class "Default")
      (node (ref "PC-1") (pin "H1_32") (pinfunction "H1_32_H1_32") (pintype "passive"))
    )
    (net (code "114") (name "unconnected-(PC-1-PadH1_33)") (class "Default")
      (node (ref "PC-1") (pin "H1_33") (pinfunction "H1_33_H1_33") (pintype "passive"))
    )
    (net (code "115") (name "unconnected-(PC-1-PadH1_34)") (class "Default")
      (node (ref "PC-1") (pin "H1_34") (pinfunction "H1_34_H1_34") (pintype "passive"))
    )
    (net (code "116") (name "unconnected-(PC-1-PadH1_35)") (class "Default")
      (node (ref "PC-1") (pin "H1_35") (pinfunction "H1_35_H1_35") (pintype "passive"))
    )
    (net (code "117") (name "unconnected-(PC-1-PadH1_36)") (class "Default")
      (node (ref "PC-1") (pin "H1_36") (pinfunction "H1_36_H1_36") (pintype "passive"))
    )
    (net (code "118") (name "unconnected-(PC-1-PadH1_37)") (class "Default")
      (node (ref "PC-1") (pin "H1_37") (pinfunction "H1_37_H1_37") (pintype "passive"))
    )
    (net (code "119") (name "unconnected-(PC-1-PadH1_38)") (class "Default")
      (node (ref "PC-1") (pin "H1_38") (pinfunction "H1_38_H1_38") (pintype "passive"))
    )
    (net (code "120") (name "unconnected-(PC-1-PadH1_39)") (class "Default")
      (node (ref "PC-1") (pin "H1_39") (pinfunction "H1_39_H1_39") (pintype "passive"))
    )
    (net (code "121") (name "unconnected-(PC-1-PadH1_40)") (class "Default")
      (node (ref "PC-1") (pin "H1_40") (pinfunction "H1_40_H1_40") (pintype "passive"))
    )
    (net (code "122") (name "unconnected-(PC-1-PadH1_41)") (class "Default")
      (node (ref "PC-1") (pin "H1_41") (pinfunction "H1_41_H1_41") (pintype "passive"))
    )
    (net (code "123") (name "unconnected-(PC-1-PadH1_42)") (class "Default")
      (node (ref "PC-1") (pin "H1_42") (pinfunction "H1_42_H1_42") (pintype "passive"))
    )
    (net (code "124") (name "unconnected-(PC-1-PadH1_43)") (class "Default")
      (node (ref "PC-1") (pin "H1_43") (pinfunction "H1_43_H1_43") (pintype "passive"))
    )
    (net (code "125") (name "unconnected-(PC-1-PadH1_44)") (class "Default")
      (node (ref "PC-1") (pin "H1_44") (pinfunction "H1_44_H1_44") (pintype "passive"))
    )
    (net (code "126") (name "unconnected-(PC-1-PadH1_45)") (class "Default")
      (node (ref "PC-1") (pin "H1_45") (pinfunction "H1_45_H1_45") (pintype "passive"))
    )
    (net (code "127") (name "unconnected-(PC-1-PadH1_46)") (class "Default")
      (node (ref "PC-1") (pin "H1_46") (pinfunction "H1_46_H1_46") (pintype "passive"))
    )
    (net (code "128") (name "unconnected-(PC-1-PadH1_47)") (class "Default")
      (node (ref "PC-1") (pin "H1_47") (pinfunction "H1_47_H1_47") (pintype "passive"))
    )
    (net (code "129") (name "unconnected-(PC-1-PadH1_48)") (class "Default")
      (node (ref "PC-1") (pin "H1_48") (pinfunction "H1_48_H1_48") (pintype "passive"))
    )
    (net (code "130") (name "unconnected-(PC-1-PadH1_49)") (class "Default")
      (node (ref "PC-1") (pin "H1_49") (pinfunction "H1_49_H1_49") (pintype "passive"))
    )
    (net (code "131") (name "unconnected-(PC-1-PadH1_50)") (class "Default")
      (node (ref "PC-1") (pin "H1_50") (pinfunction "H1_50_H1_50") (pintype "passive"))
    )
    (net (code "132") (name "unconnected-(PC-1-PadH2_1)") (class "Default")
      (node (ref "PC-1") (pin "H2_1") (pinfunction "H2_1_H2_1") (pintype "passive"))
    )
    (net (code "133") (name "unconnected-(PC-1-PadH2_2)") (class "Default")
      (node (ref "PC-1") (pin "H2_2") (pinfunction "H2_2_H2_2") (pintype "passive"))
    )
    (net (code "134") (name "unconnected-(PC-1-PadH2_3)") (class "Default")
      (node (ref "PC-1") (pin "H2_3") (pinfunction "H2_3_H2_3") (pintype "passive"))
    )
    (net (code "135") (name "unconnected-(PC-1-PadH2_4)") (class "Default")
      (node (ref "PC-1") (pin "H2_4") (pinfunction "H2_4_H2_4") (pintype "passive"))
    )
    (net (code "136") (name "unconnected-(PC-1-PadH2_5)") (class "Default")
      (node (ref "PC-1") (pin "H2_5") (pinfunction "H2_5_H2_5") (pintype "passive"))
    )
    (net (code "137") (name "unconnected-(PC-1-PadH2_6)") (class "Default")
      (node (ref "PC-1") (pin "H2_6") (pinfunction "H2_6_H2_6") (pintype "passive"))
    )
    (net (code "138") (name "unconnected-(PC-1-PadH2_7)") (class "Default")
      (node (ref "PC-1") (pin "H2_7") (pinfunction "H2_7_H2_7") (pintype "passive"))
    )
    (net (code "139") (name "unconnected-(PC-1-PadH2_8)") (class "Default")
      (node (ref "PC-1") (pin "H2_8") (pinfunction "H2_8_H2_8") (pintype "passive"))
    )
    (net (code "140") (name "unconnected-(PC-1-PadH2_9)") (class "Default")
      (node (ref "PC-1") (pin "H2_9") (pinfunction "H2_9_H2_9") (pintype "passive"))
    )
    (net (code "141") (name "unconnected-(PC-1-PadH2_10)") (class "Default")
      (node (ref "PC-1") (pin "H2_10") (pinfunction "H2_10_H2_10") (pintype "passive"))
    )
    (net (code "142") (name "unconnected-(PC-1-PadH2_11)") (class "Default")
      (node (ref "PC-1") (pin "H2_11") (pinfunction "H2_11_H2_11") (pintype "passive"))
    )
    (net (code "143") (name "unconnected-(PC-1-PadH2_12)") (class "Default")
      (node (ref "PC-1") (pin "H2_12") (pinfunction "H2_12_H2_12") (pintype "passive"))
    )
    (net (code "144") (name "unconnected-(PC-1-PadH2_13)") (class "Default")
      (node (ref "PC-1") (pin "H2_13") (pinfunction "H2_13_H2_13") (pintype "passive"))
    )
    (net (code "145") (name "unconnected-(PC-1-PadH2_14)") (class "Default")
      (node (ref "PC-1") (pin "H2_14") (pinfunction "H2_14_H2_14") (pintype "passive"))
    )
    (net (code "146") (name "unconnected-(PC-1-PadH2_15)") (class "Default")
      (node (ref "PC-1") (pin "H2_15") (pinfunction "H2_15_H2_15") (pintype "passive"))
    )
    (net (code "147") (name "unconnected-(PC-1-PadH2_16)") (class "Default")
      (node (ref "PC-1") (pin "H2_16") (pinfunction "H2_16_H2_16") (pintype "passive"))
    )
    (net (code "148") (name "unconnected-(PC-1-PadH2_17)") (class "Default")
      (node (ref "PC-1") (pin "H2_17") (pinfunction "H2_17_H2_17") (pintype "passive"))
    )
    (net (code "149") (name "unconnected-(PC-1-PadH2_18)") (class "Default")
      (node (ref "PC-1") (pin "H2_18") (pinfunction "H2_18_H2_18") (pintype "passive"))
    )
    (net (code "150") (name "unconnected-(PC-1-PadH2_19)") (class "Default")
      (node (ref "PC-1") (pin "H2_19") (pinfunction "H2_19_H2_19") (pintype "passive"))
    )
    (net (code "151") (name "unconnected-(PC-1-PadH2_20)") (class "Default")
      (node (ref "PC-1") (pin "H2_20") (pinfunction "H2_20_H2_20") (pintype "passive"))
    )
    (net (code "152") (name "unconnected-(PC-1-PadH2_21)") (class "Default")
      (node (ref "PC-1") (pin "H2_21") (pinfunction "H2_21_H2_21") (pintype "passive"))
    )
    (net (code "153") (name "unconnected-(PC-1-PadH2_22)") (class "Default")
      (node (ref "PC-1") (pin "H2_22") (pinfunction "H2_22_H2_22") (pintype "passive"))
    )
    (net (code "154") (name "unconnected-(PC-1-PadH2_23)") (class "Default")
      (node (ref "PC-1") (pin "H2_23") (pinfunction "H2_23_H2_23") (pintype "passive"))
    )
    (net (code "155") (name "unconnected-(PC-1-PadH2_24)") (class "Default")
      (node (ref "PC-1") (pin "H2_24") (pinfunction "H2_24_H2_24") (pintype "passive"))
    )
    (net (code "156") (name "unconnected-(PC-1-PadH2_25)") (class "Default")
      (node (ref "PC-1") (pin "H2_25") (pinfunction "H2_25_H2_25") (pintype "passive"))
    )
    (net (code "157") (name "unconnected-(PC-1-PadH2_26)") (class "Default")
      (node (ref "PC-1") (pin "H2_26") (pinfunction "H2_26_H2_26") (pintype "passive"))
    )
    (net (code "158") (name "unconnected-(PC-1-PadH2_27)") (class "Default")
      (node (ref "PC-1") (pin "H2_27") (pinfunction "H2_27_H2_27") (pintype "passive"))
    )
    (net (code "159") (name "unconnected-(PC-1-PadH2_28)") (class "Default")
      (node (ref "PC-1") (pin "H2_28") (pinfunction "H2_28_H2_28") (pintype "passive"))
    )
    (net (code "160") (name "unconnected-(PC-1-PadH2_30)") (class "Default")
      (node (ref "PC-1") (pin "H2_30") (pinfunction "H2_30_H2_30") (pintype "passive"))
    )
    (net (code "161") (name "unconnected-(PC-1-PadH2_31)") (class "Default")
      (node (ref "PC-1") (pin "H2_31") (pinfunction "H2_31_H2_31") (pintype "passive"))
    )
    (net (code "162") (name "unconnected-(PC-1-PadH2_32)") (class "Default")
      (node (ref "PC-1") (pin "H2_32") (pinfunction "H2_32_H2_32") (pintype "passive"))
    )
    (net (code "163") (name "unconnected-(PC-1-PadH2_33)") (class "Default")
      (node (ref "PC-1") (pin "H2_33") (pinfunction "H2_33_H2_33") (pintype "passive"))
    )
    (net (code "164") (name "unconnected-(PC-1-PadH2_34)") (class "Default")
      (node (ref "PC-1") (pin "H2_34") (pinfunction "H2_34_H2_34") (pintype "passive"))
    )
    (net (code "165") (name "unconnected-(PC-1-PadH2_35)") (class "Default")
      (node (ref "PC-1") (pin "H2_35") (pinfunction "H2_35_H2_35") (pintype "passive"))
    )
    (net (code "166") (name "unconnected-(PC-1-PadH2_36)") (class "Default")
      (node (ref "PC-1") (pin "H2_36") (pinfunction "H2_36_H2_36") (pintype "passive"))
    )
    (net (code "167") (name "unconnected-(PC-1-PadH2_37)") (class "Default")
      (node (ref "PC-1") (pin "H2_37") (pinfunction "H2_37_H2_37") (pintype "passive"))
    )
    (net (code "168") (name "unconnected-(PC-1-PadH2_38)") (class "Default")
      (node (ref "PC-1") (pin "H2_38") (pinfunction "H2_38_H2_38") (pintype "passive"))
    )
    (net (code "169") (name "unconnected-(PC-1-PadH2_39)") (class "Default")
      (node (ref "PC-1") (pin "H2_39") (pinfunction "H2_39_H2_39") (pintype "passive"))
    )
    (net (code "170") (name "unconnected-(PC-1-PadH2_40)") (class "Default")
      (node (ref "PC-1") (pin "H2_40") (pinfunction "H2_40_H2_40") (pintype "passive"))
    )
    (net (code "171") (name "unconnected-(PC-1-PadH2_41)") (class "Default")
      (node (ref "PC-1") (pin "H2_41") (pinfunction "H2_41_H2_41") (pintype "passive"))
    )
    (net (code "172") (name "unconnected-(PC-1-PadH2_42)") (class "Default")
      (node (ref "PC-1") (pin "H2_42") (pinfunction "H2_42_H2_42") (pintype "passive"))
    )
    (net (code "173") (name "unconnected-(PC-1-PadH2_43)") (class "Default")
      (node (ref "PC-1") (pin "H2_43") (pinfunction "H2_43_H2_43") (pintype "passive"))
    )
    (net (code "174") (name "unconnected-(PC-1-PadH2_44)") (class "Default")
      (node (ref "PC-1") (pin "H2_44") (pinfunction "H2_44_H2_44") (pintype "passive"))
    )
    (net (code "175") (name "unconnected-(PC-1-PadH2_45)") (class "Default")
      (node (ref "PC-1") (pin "H2_45") (pinfunction "H2_45_H2_45") (pintype "passive"))
    )
    (net (code "176") (name "unconnected-(PC-1-PadH2_46)") (class "Default")
      (node (ref "PC-1") (pin "H2_46") (pinfunction "H2_46_H2_46") (pintype "passive"))
    )
    (net (code "177") (name "unconnected-(PC-1-PadH2_47)") (class "Default")
      (node (ref "PC-1") (pin "H2_47") (pinfunction "H2_47_H2_47") (pintype "passive"))
    )
    (net (code "178") (name "unconnected-(PC-1-PadH2_48)") (class "Default")
      (node (ref "PC-1") (pin "H2_48") (pinfunction "H2_48_H2_48") (pintype "passive"))
    )
    (net (code "179") (name "unconnected-(PC-1-PadH2_49)") (class "Default")
      (node (ref "PC-1") (pin "H2_49") (pinfunction "H2_49_H2_49") (pintype "passive"))
    )
    (net (code "180") (name "unconnected-(PC-1-PadH2_50)") (class "Default")
      (node (ref "PC-1") (pin "H2_50") (pinfunction "H2_50_H2_50") (pintype "passive"))
    )
    (net (code "181") (name "unconnected-(PC-1-PadH2_51)") (class "Default")
      (node (ref "PC-1") (pin "H2_51") (pinfunction "H2_51_H2_51") (pintype "passive"))
    )
    (net (code "182") (name "unconnected-(PC-1-PadH2_52)") (class "Default")
      (node (ref "PC-1") (pin "H2_52") (pinfunction "H2_52_H2_52") (pintype "passive"))
    )
  )
)
